# nano2.net
KiCad netlist of a schematic drawn in EAGLE
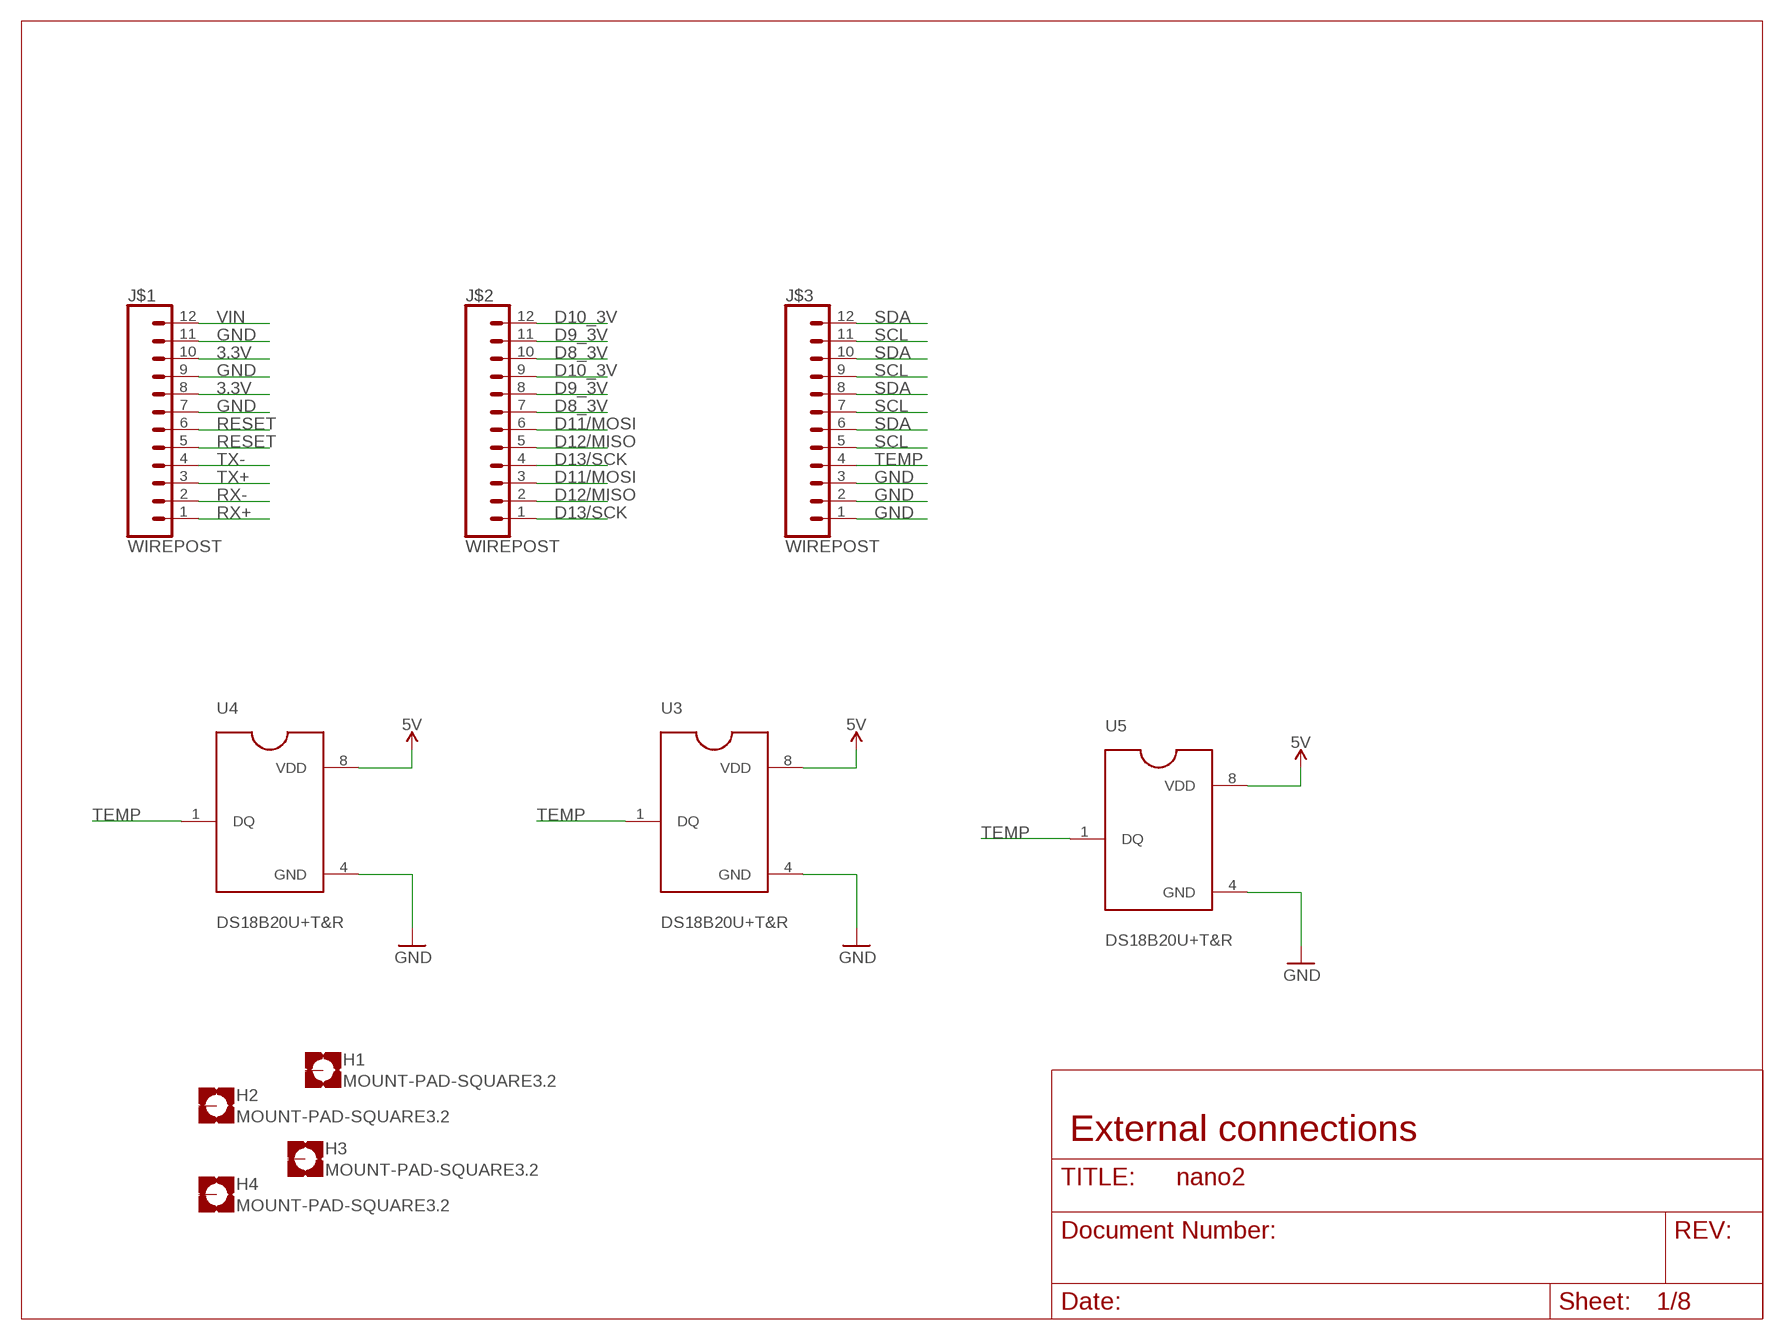
[diagram p0: schematic, sheet 1]
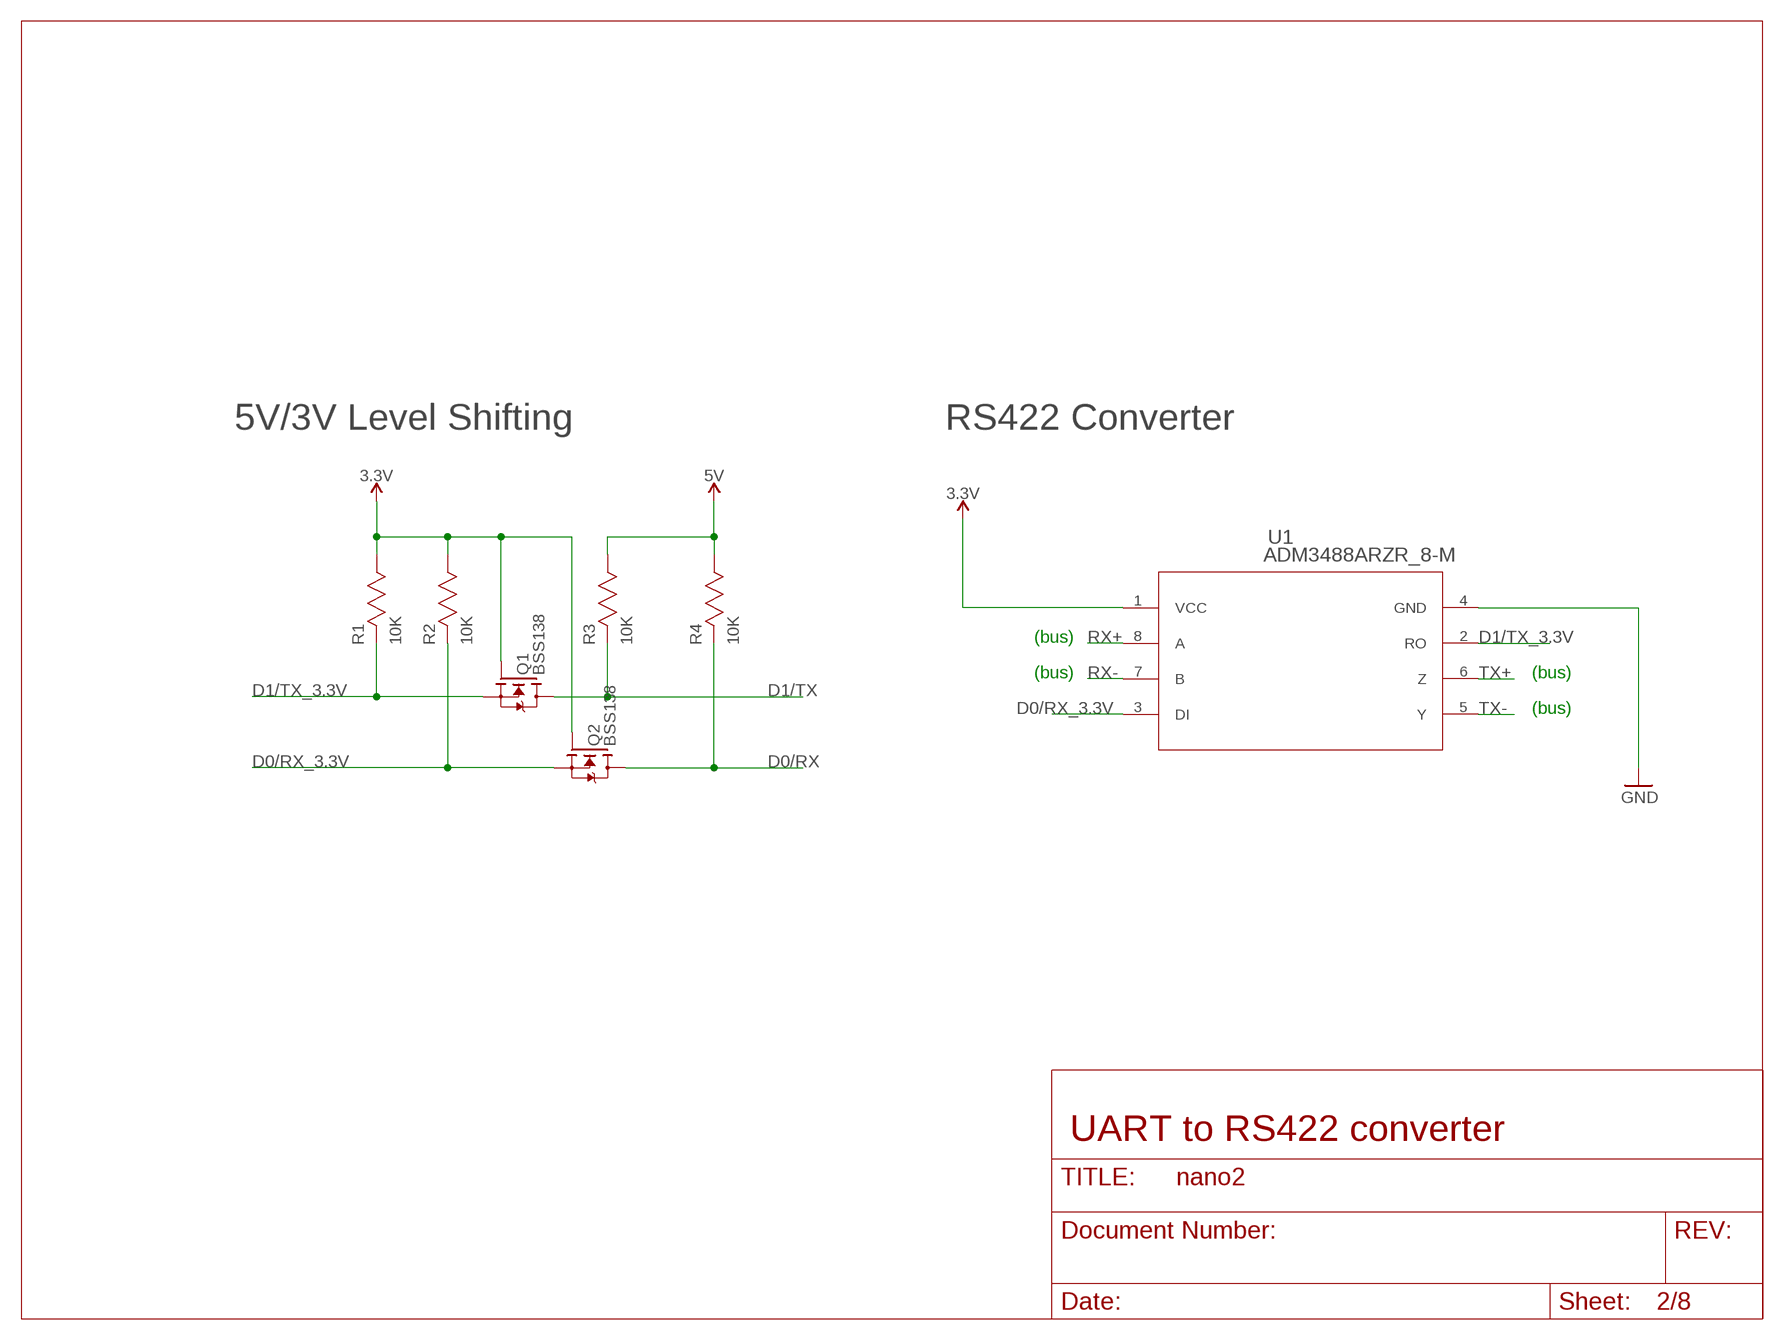
[diagram p1: schematic, sheet 2]
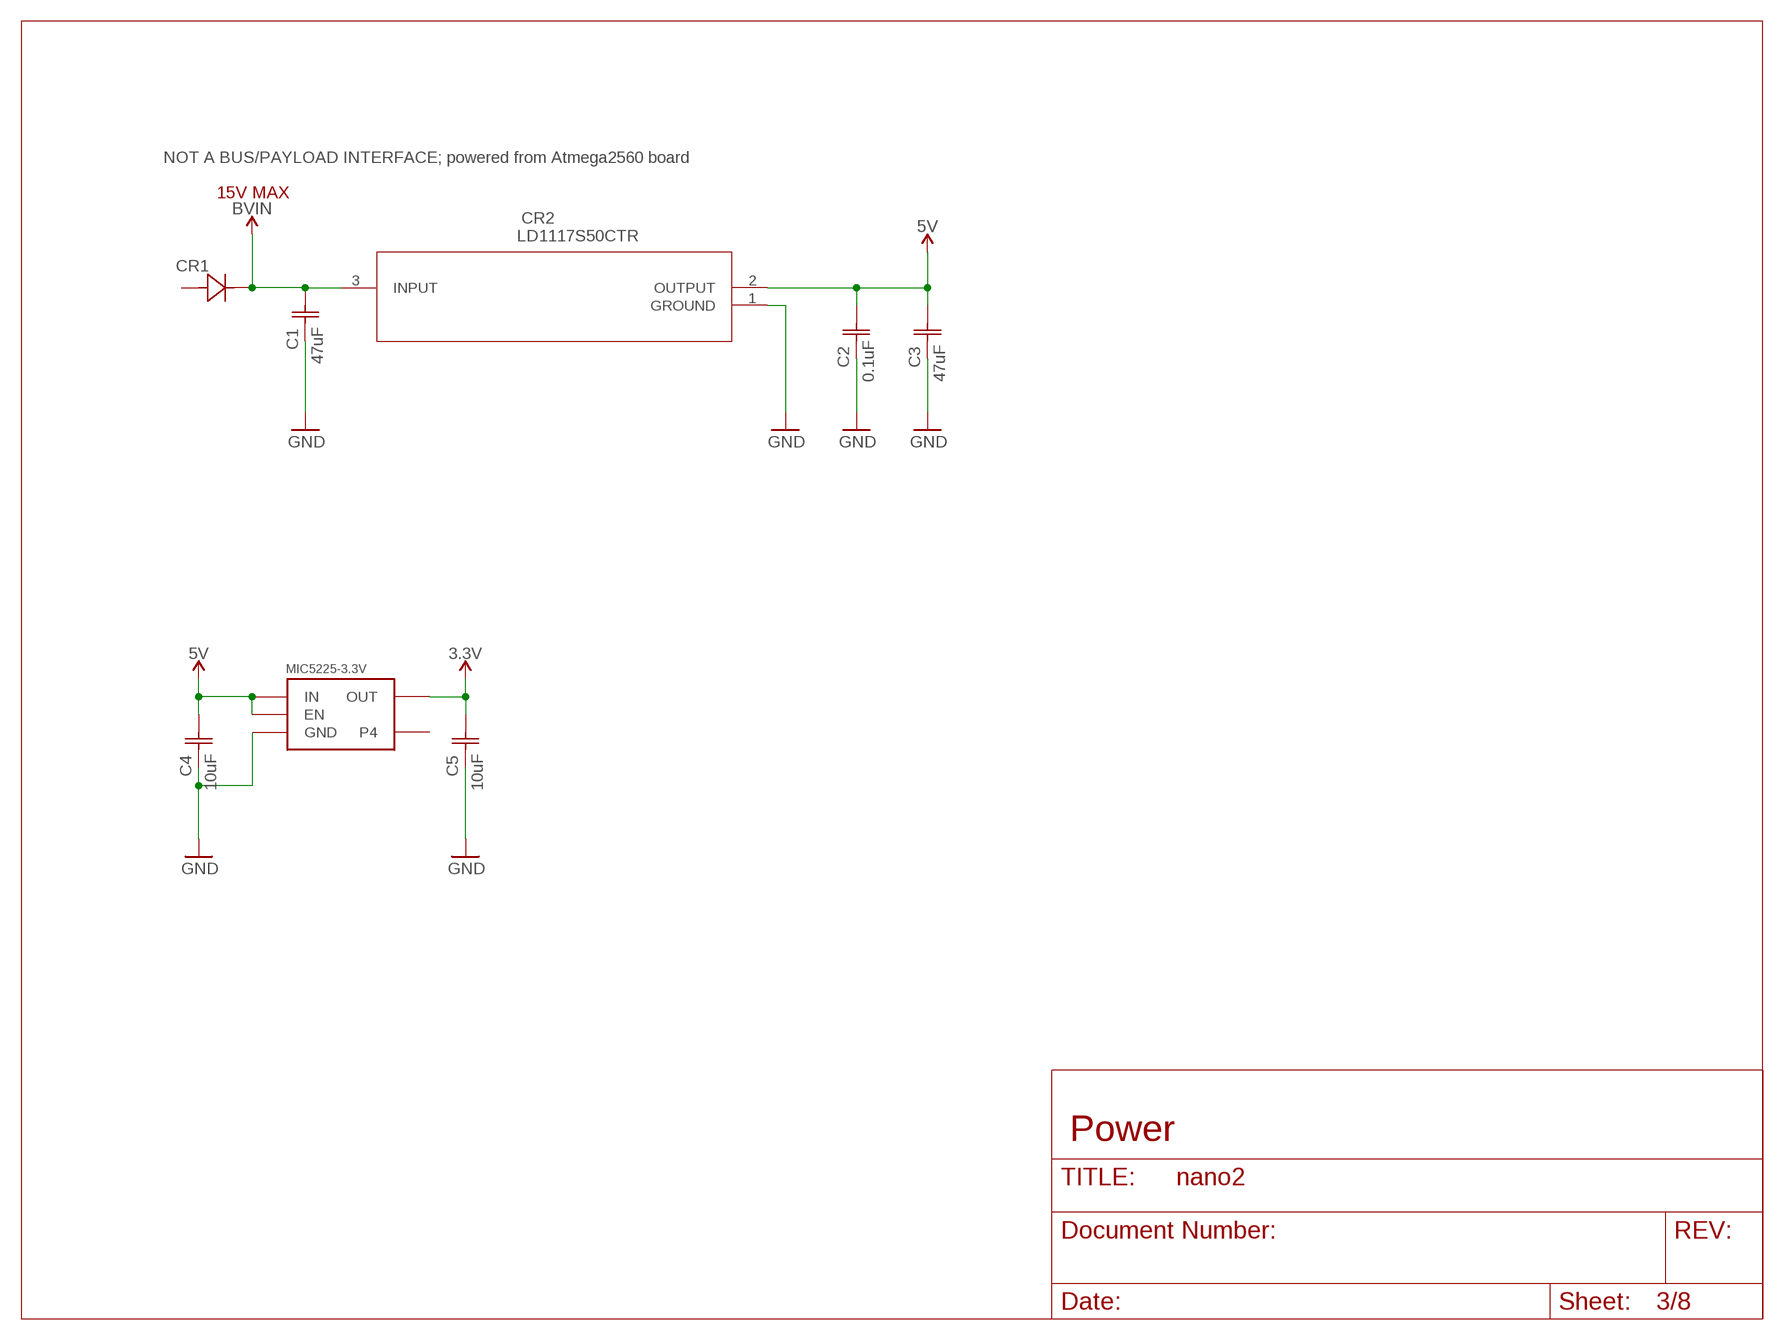
[diagram p2: schematic, sheet 3]
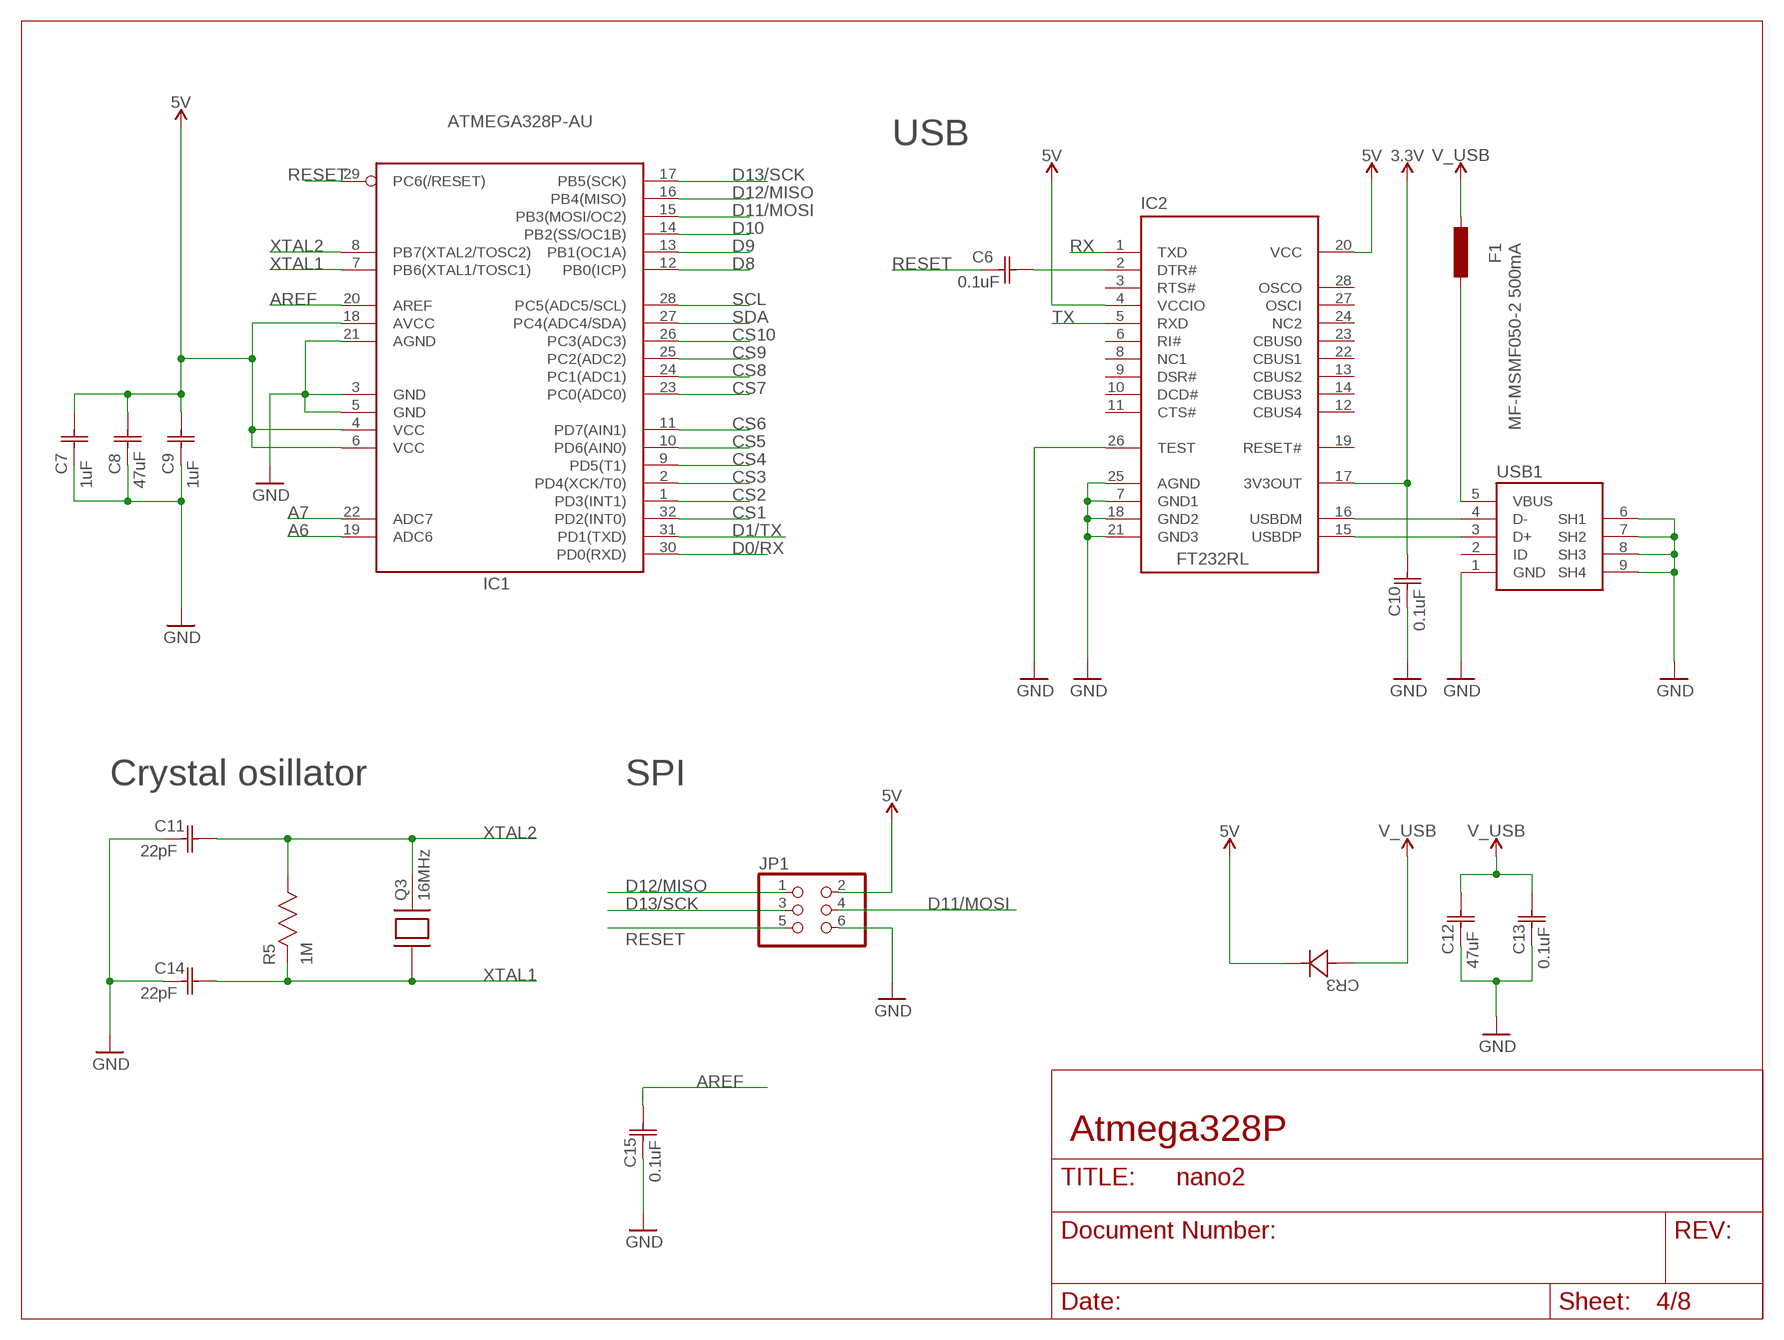
[diagram p3: schematic, sheet 4]
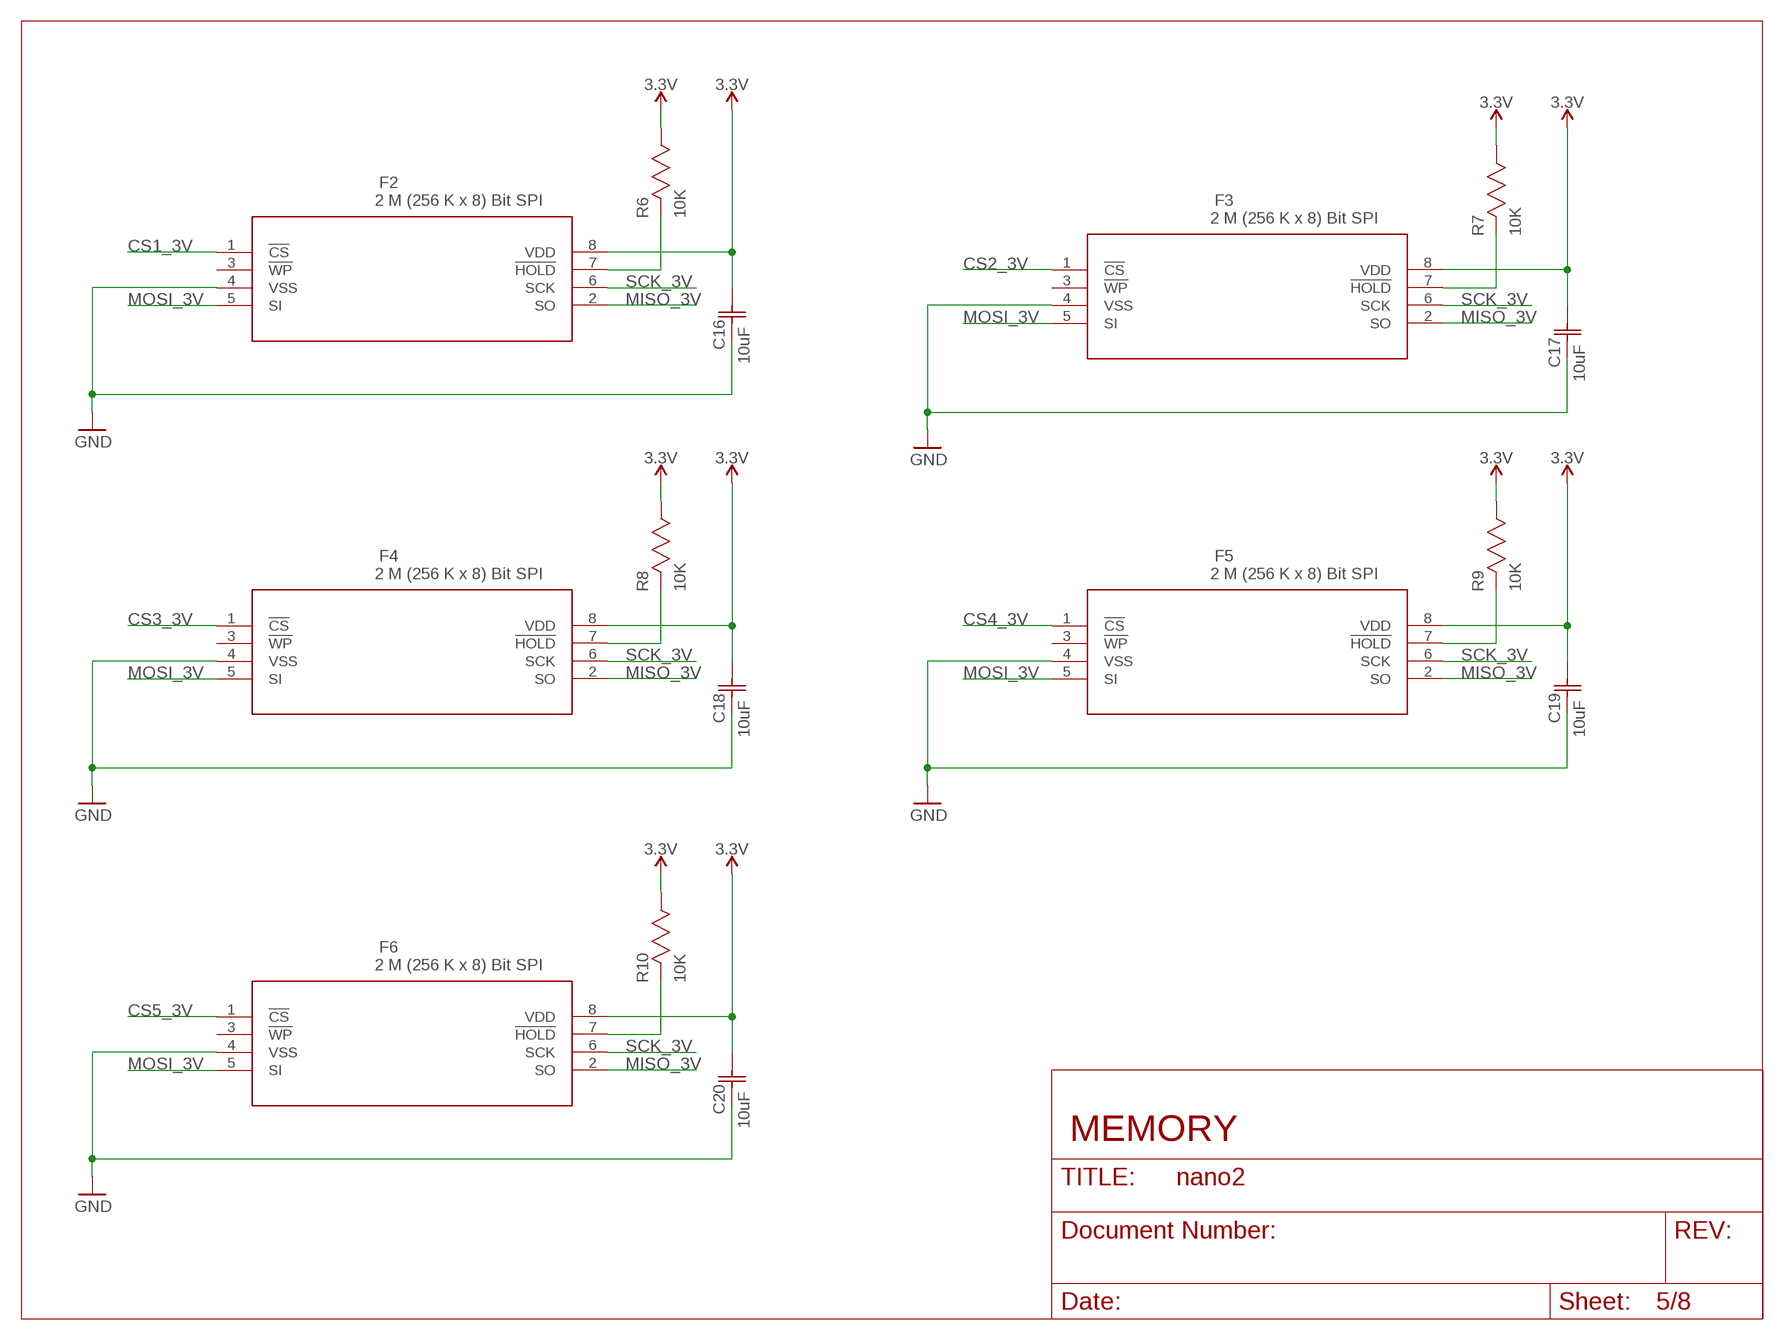
[diagram p4: schematic, sheet 5]
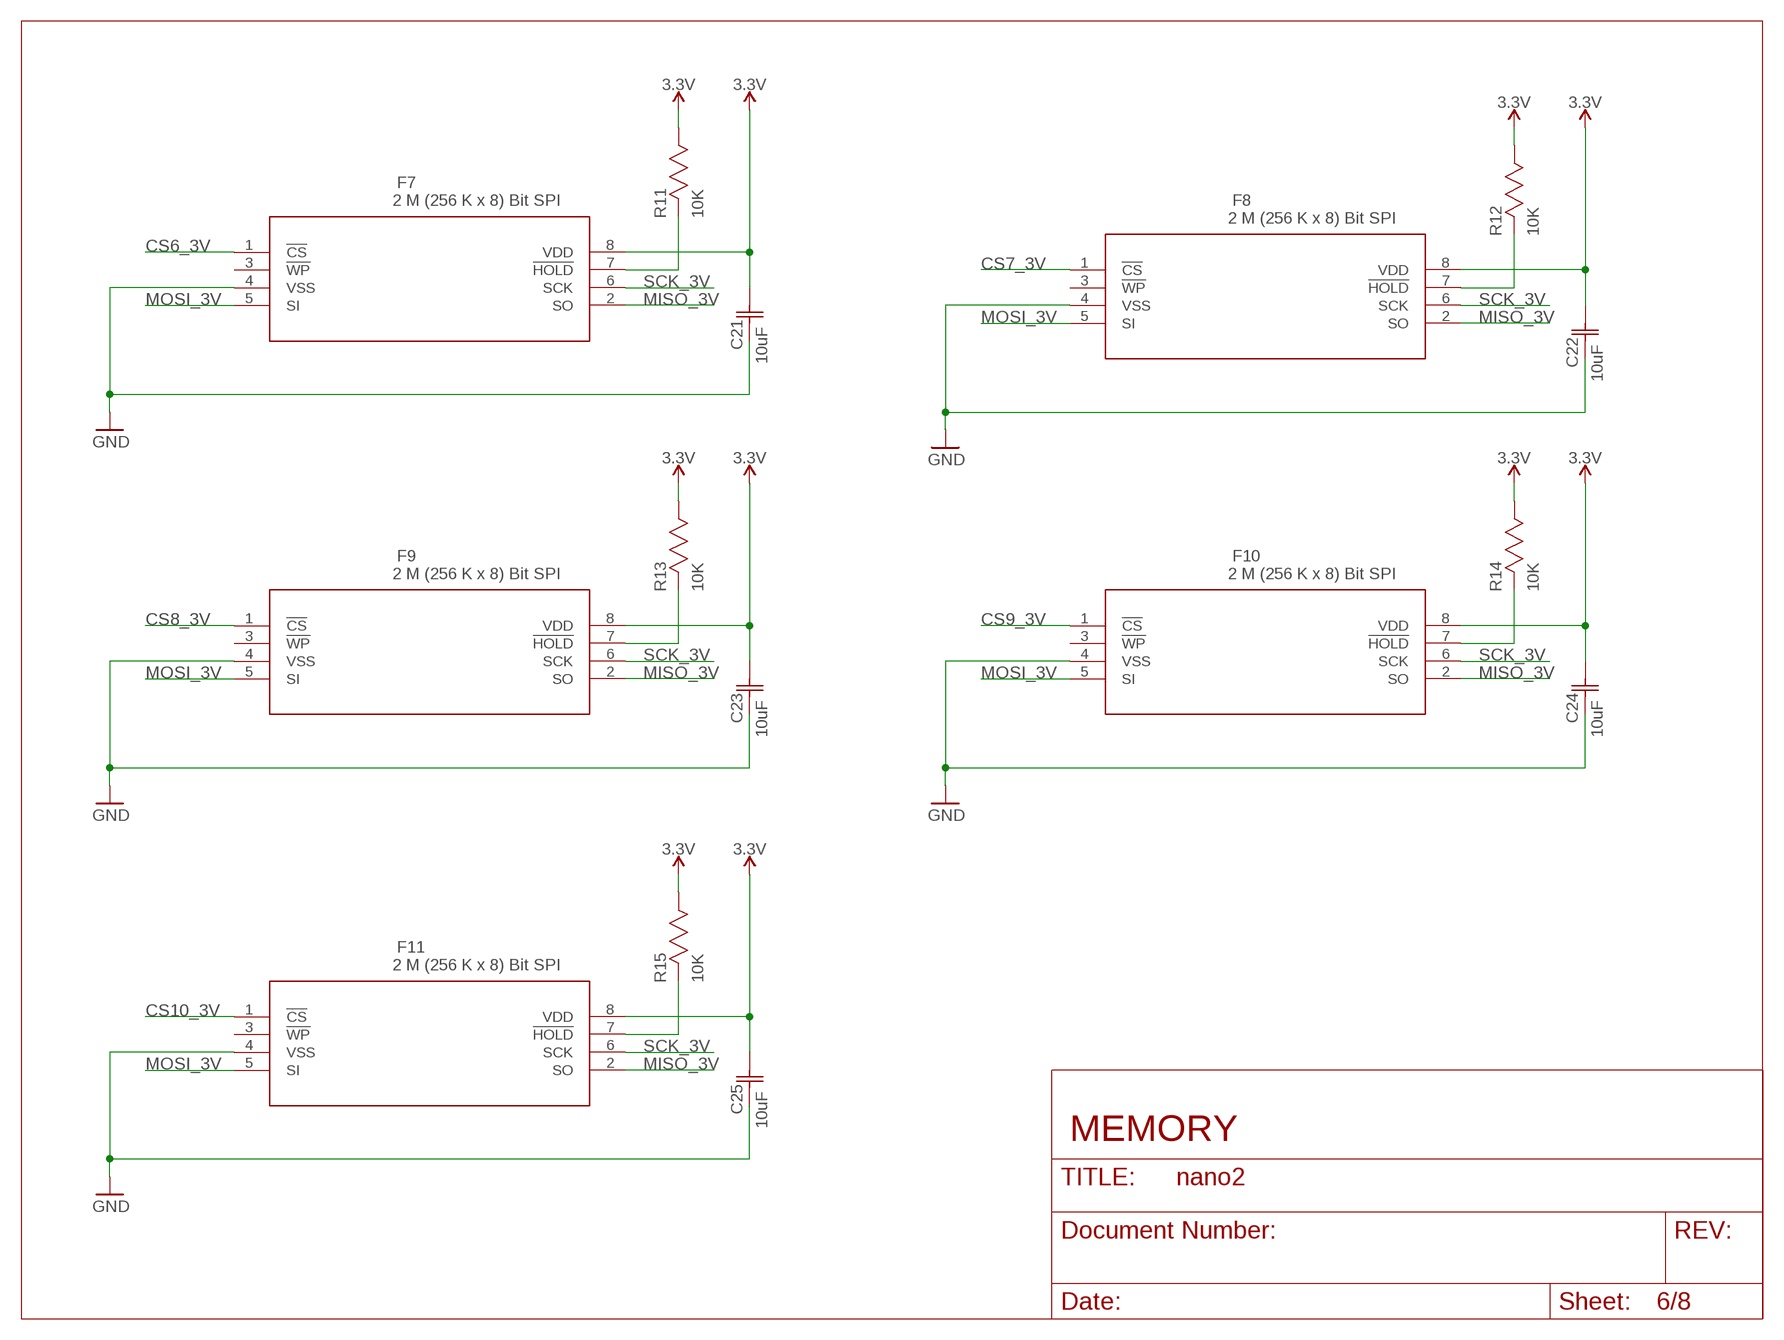
[diagram p5: schematic, sheet 6]
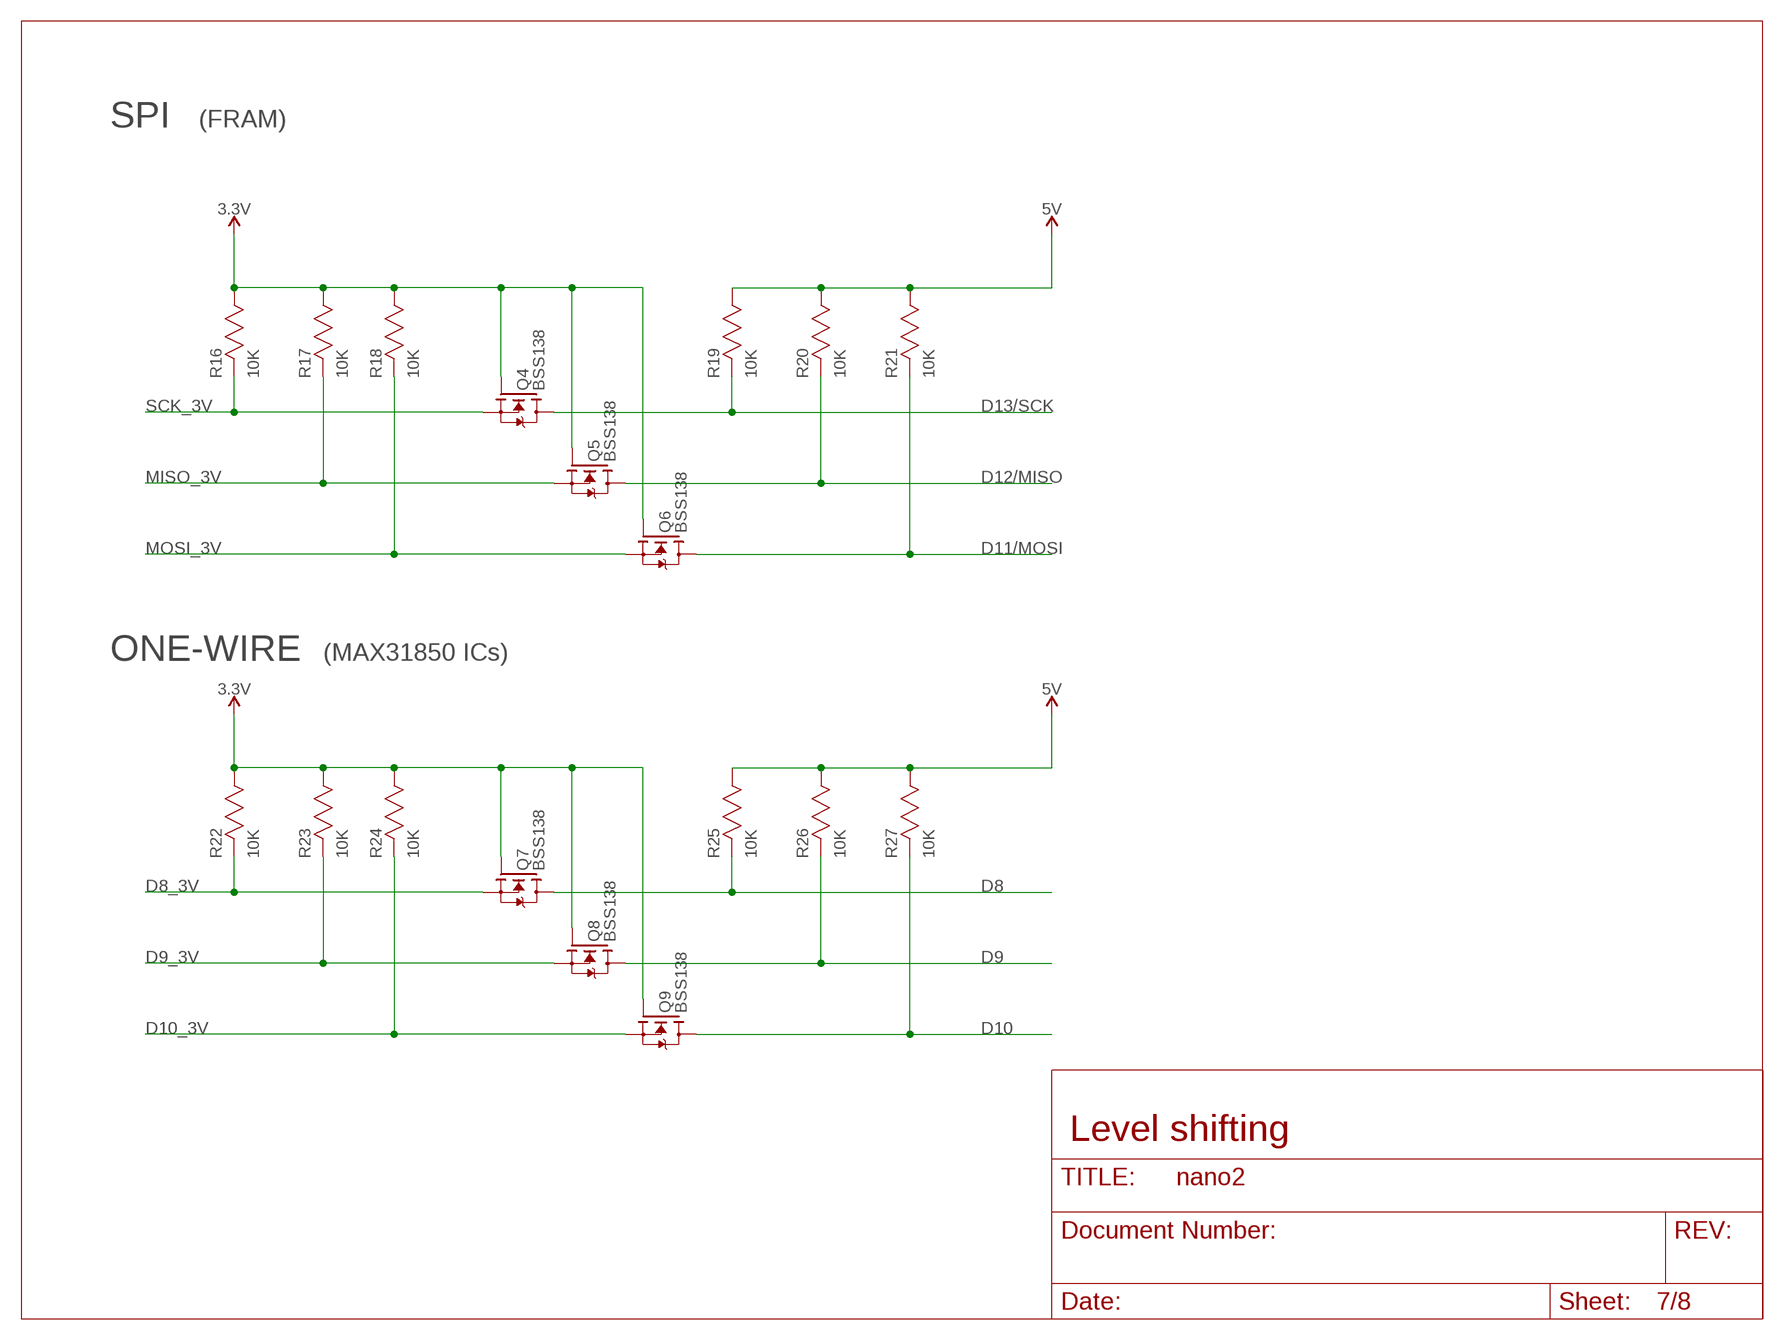
[diagram p6: schematic, sheet 7]
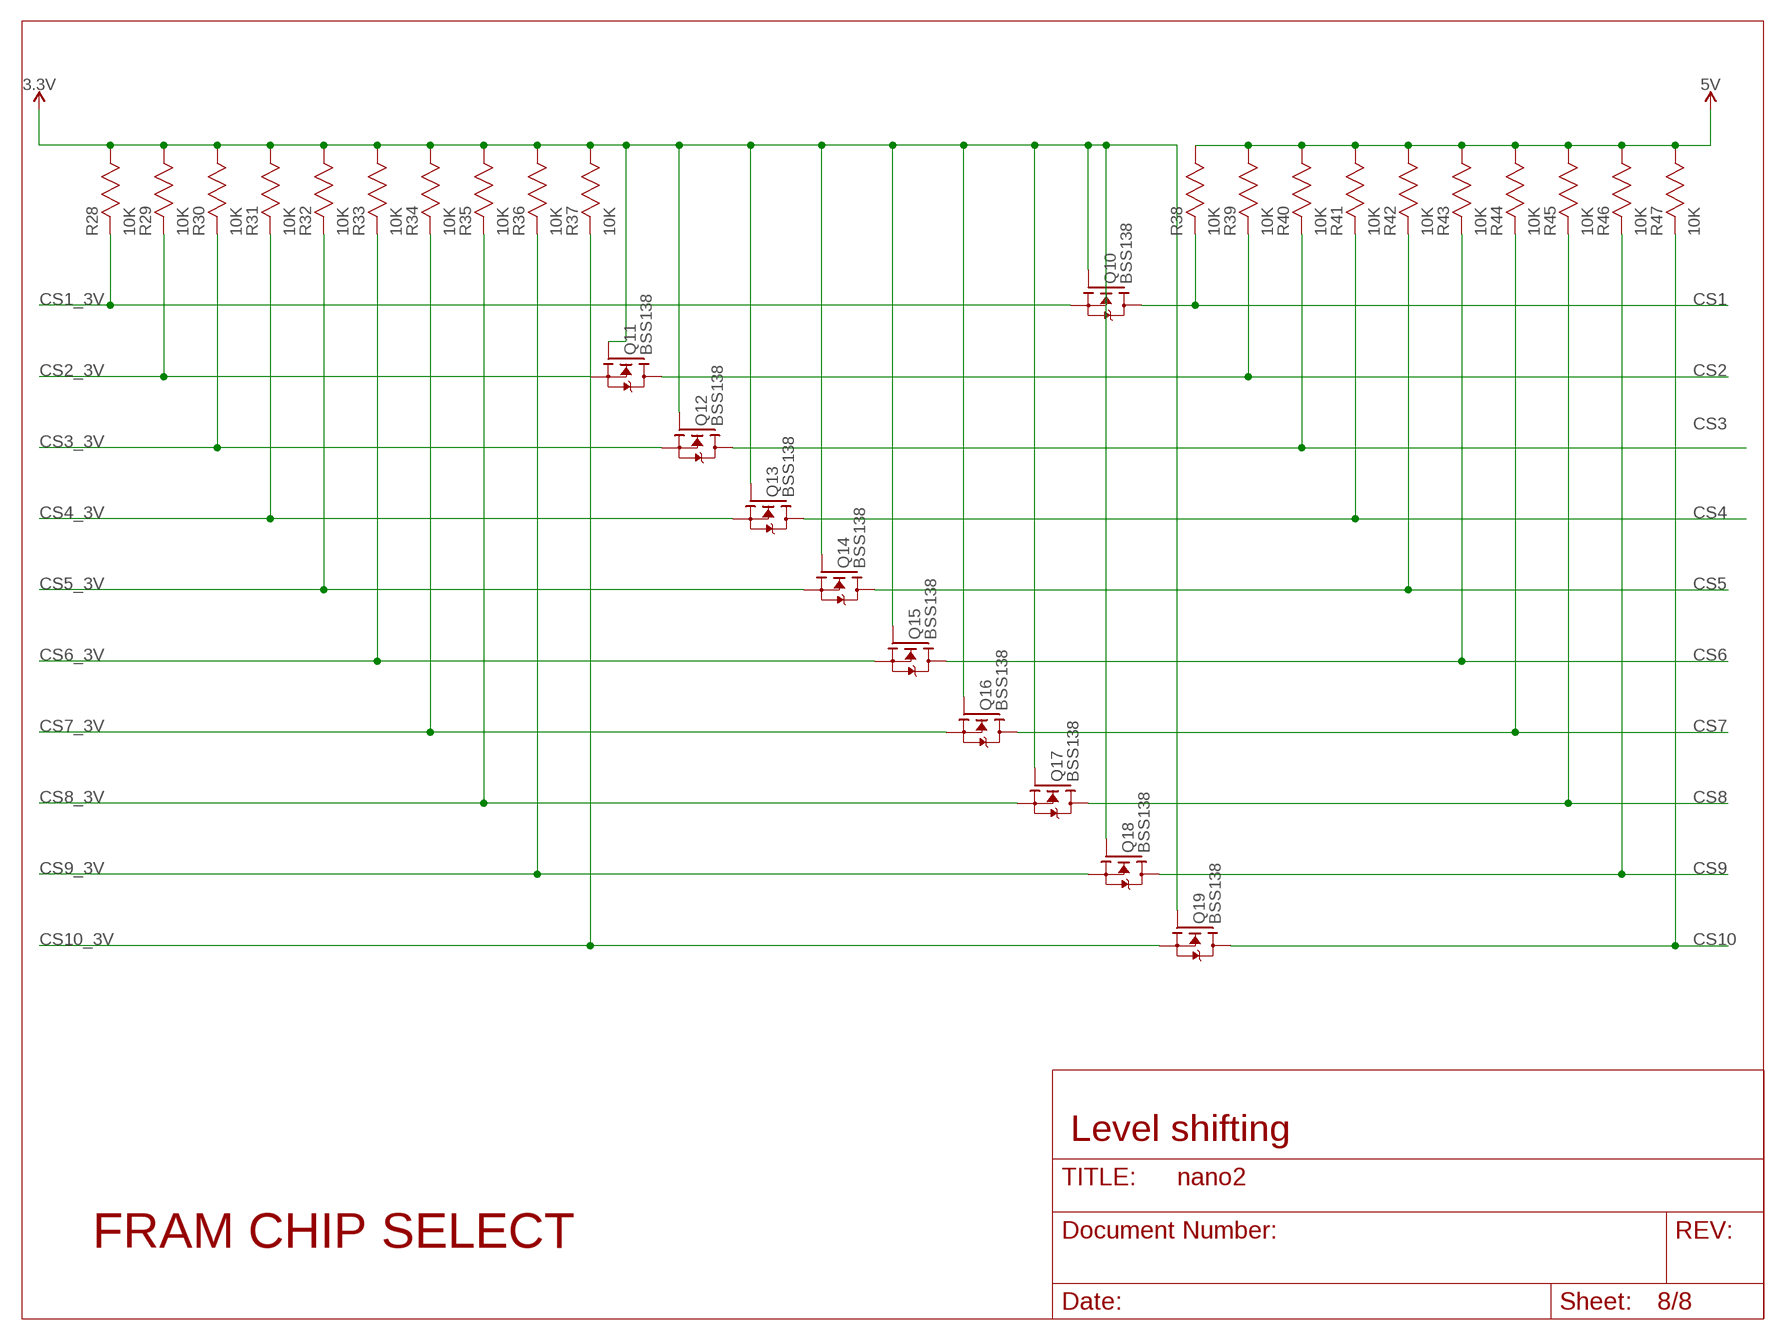
[diagram p7: schematic, sheet 8]

(export (version "E")
  (design (tool "Eeschema 10.0.6"))
  (components
    (comp (ref "C6")
      (value "0.1uF")
      (footprint "eagle-import:CAP_01")
      (fields (field (name "MANUFACTURER_PART_NUMBER") "CC0402KRX5R6BB104"))
      (libsource (lib "eagle-import") (part "CAP_01UF"))
    )
    (comp (ref "C7")
      (value "1uF")
      (footprint "eagle-import:YAG_CC0805")
      (fields (field (name "MANUFACTURER_PART_NUMBER") "CC0805KKX7R7BB105"))
      (libsource (lib "eagle-import") (part "CAP_1UF"))
    )
    (comp (ref "C8")
      (value "47uF")
      (footprint "eagle-import:CAP_5750")
      (fields (field (name "MANUFACTURER_PART_NUMBER") "CGA9N3X7R1C476M230KB"))
      (libsource (lib "eagle-import") (part "CAP_47UF"))
    )
    (comp (ref "C9")
      (value "1uF")
      (footprint "eagle-import:YAG_CC0805")
      (fields (field (name "MANUFACTURER_PART_NUMBER") "CC0805KKX7R7BB105"))
      (libsource (lib "eagle-import") (part "CAP_1UF"))
    )
    (comp (ref "C10")
      (value "0.1uF")
      (footprint "eagle-import:CAP_01")
      (fields (field (name "MANUFACTURER_PART_NUMBER") "CC0402KRX5R6BB104"))
      (libsource (lib "eagle-import") (part "CAP_01UF"))
    )
    (comp (ref "C11")
      (value "22pF")
      (footprint "eagle-import:CC0805N")
      (libsource (lib "eagle-import") (part "CAP_22PF"))
    )
    (comp (ref "C12")
      (value "47uF")
      (footprint "eagle-import:CAP_5750")
      (fields (field (name "MANUFACTURER_PART_NUMBER") "CGA9N3X7R1C476M230KB"))
      (libsource (lib "eagle-import") (part "CAP_47UF"))
    )
    (comp (ref "C13")
      (value "0.1uF")
      (footprint "eagle-import:CAP_01")
      (fields (field (name "MANUFACTURER_PART_NUMBER") "CC0402KRX5R6BB104"))
      (libsource (lib "eagle-import") (part "CAP_01UF"))
    )
    (comp (ref "C14")
      (value "22pF")
      (footprint "eagle-import:CC0805N")
      (libsource (lib "eagle-import") (part "CAP_22PF"))
    )
    (comp (ref "C15")
      (value "0.1uF")
      (footprint "eagle-import:CAP_01")
      (fields (field (name "MANUFACTURER_PART_NUMBER") "CC0402KRX5R6BB104"))
      (libsource (lib "eagle-import") (part "CAP_01UF"))
    )
    (comp (ref "CR3")
      (value "DIODE_600V_3A")
      (footprint "eagle-import:DIODE_600V_3A")
      (fields (field (name "MANUFACTURER_PART_NUMBER") "RS3JB13F"))
      (libsource (lib "eagle-import") (part "DIODE_600V_3A"))
    )
    (comp (ref "F1")
      (value "MF-MSMF050-2 500mA")
      (footprint "eagle-import:L1812")
      (fields (field (name "PART_NUMBER") "MF-MSMF050-2"))
      (libsource (lib "eagle-import") (part "0002_MF-MSMF050-2"))
    )
    (comp (ref "IC1")
      (value "ATMEGA328P-AU")
      (footprint "eagle-import:TQFP32-08")
      (libsource (lib "eagle-import") (part "0265_ATMEGA328P-AU"))
    )
    (comp (ref "IC2")
      (value "FT232RL")
      (footprint "eagle-import:SSOP28")
      (libsource (lib "eagle-import") (part "0226_FT232RL"))
    )
    (comp (ref "JP1")
      (value "0114_PH254-203DF118A00V")
      (footprint "eagle-import:2X03")
      (fields (field (name "PART_NUMBER") "PH254-203DF118A00V"))
      (libsource (lib "eagle-import") (part "0114_PH254-203DF118A00V"))
    )
    (comp (ref "Q3")
      (value "16MHz")
      (footprint "eagle-import:OSCILLATOR")
      (libsource (lib "eagle-import") (part "OSILLATOR"))
    )
    (comp (ref "R5")
      (value "1M")
      (footprint "eagle-import:RC0603N")
      (libsource (lib "eagle-import") (part "RES_1M"))
    )
    (comp (ref "USB1")
      (value "0219_14850")
      (footprint "eagle-import:USB-MINI-B_2")
      (fields (field (name "PART_NUMBER") "14850"))
      (libsource (lib "eagle-import") (part "0219_14850"))
    )
    (comp (ref "Q1")
      (value "BSS138")
      (footprint "eagle-import:SOT-23")
      (fields (field (name "MANUFACTURER_PART_NUMBER") "BSS138TA"))
      (libsource (lib "eagle-import") (part "BSS138"))
    )
    (comp (ref "Q2")
      (value "BSS138")
      (footprint "eagle-import:SOT-23")
      (fields (field (name "MANUFACTURER_PART_NUMBER") "BSS138TA"))
      (libsource (lib "eagle-import") (part "BSS138"))
    )
    (comp (ref "R1")
      (value "10K")
      (footprint "eagle-import:RC0603N")
      (libsource (lib "eagle-import") (part "RES_10K"))
    )
    (comp (ref "R2")
      (value "10K")
      (footprint "eagle-import:RC0603N")
      (libsource (lib "eagle-import") (part "RES_10K"))
    )
    (comp (ref "R3")
      (value "10K")
      (footprint "eagle-import:RC0603N")
      (libsource (lib "eagle-import") (part "RES_10K"))
    )
    (comp (ref "R4")
      (value "10K")
      (footprint "eagle-import:RC0603N")
      (libsource (lib "eagle-import") (part "RES_10K"))
    )
    (comp (ref "U1")
      (value "ADM3488ARZR_8-M")
      (footprint "eagle-import:R_8-M")
      (fields (field (name "MANUFACTURER_PART_NUMBER") "ADM3488ARZ"))
      (libsource (lib "eagle-import") (part "ADM3488ARZR_8-M"))
    )
    (comp (ref "C16")
      (value "10uF")
      (footprint "eagle-import:CAP_GRM219R61A106KE44D")
      (libsource (lib "eagle-import") (part "CAP_10UF"))
    )
    (comp (ref "C17")
      (value "10uF")
      (footprint "eagle-import:CAP_GRM219R61A106KE44D")
      (libsource (lib "eagle-import") (part "CAP_10UF"))
    )
    (comp (ref "C18")
      (value "10uF")
      (footprint "eagle-import:CAP_GRM219R61A106KE44D")
      (libsource (lib "eagle-import") (part "CAP_10UF"))
    )
    (comp (ref "C19")
      (value "10uF")
      (footprint "eagle-import:CAP_GRM219R61A106KE44D")
      (libsource (lib "eagle-import") (part "CAP_10UF"))
    )
    (comp (ref "C20")
      (value "10uF")
      (footprint "eagle-import:CAP_GRM219R61A106KE44D")
      (libsource (lib "eagle-import") (part "CAP_10UF"))
    )
    (comp (ref "F2")
      (value "2 M (256 K x 8) Bit SPI")
      (footprint "eagle-import:FRAM_MB85RS2MTA_FPT-8P-M09")
      (libsource (lib "eagle-import") (part "FRAM_MB85RS2MTA"))
    )
    (comp (ref "F3")
      (value "2 M (256 K x 8) Bit SPI")
      (footprint "eagle-import:FRAM_MB85RS2MTA_FPT-8P-M09")
      (libsource (lib "eagle-import") (part "FRAM_MB85RS2MTA"))
    )
    (comp (ref "F4")
      (value "2 M (256 K x 8) Bit SPI")
      (footprint "eagle-import:FRAM_MB85RS2MTA_FPT-8P-M09")
      (libsource (lib "eagle-import") (part "FRAM_MB85RS2MTA"))
    )
    (comp (ref "F5")
      (value "2 M (256 K x 8) Bit SPI")
      (footprint "eagle-import:FRAM_MB85RS2MTA_FPT-8P-M09")
      (libsource (lib "eagle-import") (part "FRAM_MB85RS2MTA"))
    )
    (comp (ref "F6")
      (value "2 M (256 K x 8) Bit SPI")
      (footprint "eagle-import:FRAM_MB85RS2MTA_FPT-8P-M09")
      (libsource (lib "eagle-import") (part "FRAM_MB85RS2MTA"))
    )
    (comp (ref "R6")
      (value "10K")
      (footprint "eagle-import:RC0603N")
      (libsource (lib "eagle-import") (part "RES_10K"))
    )
    (comp (ref "R7")
      (value "10K")
      (footprint "eagle-import:RC0603N")
      (libsource (lib "eagle-import") (part "RES_10K"))
    )
    (comp (ref "R8")
      (value "10K")
      (footprint "eagle-import:RC0603N")
      (libsource (lib "eagle-import") (part "RES_10K"))
    )
    (comp (ref "R9")
      (value "10K")
      (footprint "eagle-import:RC0603N")
      (libsource (lib "eagle-import") (part "RES_10K"))
    )
    (comp (ref "R10")
      (value "10K")
      (footprint "eagle-import:RC0603N")
      (libsource (lib "eagle-import") (part "RES_10K"))
    )
    (comp (ref "C21")
      (value "10uF")
      (footprint "eagle-import:CAP_GRM219R61A106KE44D")
      (libsource (lib "eagle-import") (part "CAP_10UF"))
    )
    (comp (ref "C22")
      (value "10uF")
      (footprint "eagle-import:CAP_GRM219R61A106KE44D")
      (libsource (lib "eagle-import") (part "CAP_10UF"))
    )
    (comp (ref "C23")
      (value "10uF")
      (footprint "eagle-import:CAP_GRM219R61A106KE44D")
      (libsource (lib "eagle-import") (part "CAP_10UF"))
    )
    (comp (ref "C24")
      (value "10uF")
      (footprint "eagle-import:CAP_GRM219R61A106KE44D")
      (libsource (lib "eagle-import") (part "CAP_10UF"))
    )
    (comp (ref "C25")
      (value "10uF")
      (footprint "eagle-import:CAP_GRM219R61A106KE44D")
      (libsource (lib "eagle-import") (part "CAP_10UF"))
    )
    (comp (ref "F7")
      (value "2 M (256 K x 8) Bit SPI")
      (footprint "eagle-import:FRAM_MB85RS2MTA_FPT-8P-M09")
      (libsource (lib "eagle-import") (part "FRAM_MB85RS2MTA"))
    )
    (comp (ref "F8")
      (value "2 M (256 K x 8) Bit SPI")
      (footprint "eagle-import:FRAM_MB85RS2MTA_FPT-8P-M09")
      (libsource (lib "eagle-import") (part "FRAM_MB85RS2MTA"))
    )
    (comp (ref "F9")
      (value "2 M (256 K x 8) Bit SPI")
      (footprint "eagle-import:FRAM_MB85RS2MTA_FPT-8P-M09")
      (libsource (lib "eagle-import") (part "FRAM_MB85RS2MTA"))
    )
    (comp (ref "F10")
      (value "2 M (256 K x 8) Bit SPI")
      (footprint "eagle-import:FRAM_MB85RS2MTA_FPT-8P-M09")
      (libsource (lib "eagle-import") (part "FRAM_MB85RS2MTA"))
    )
    (comp (ref "F11")
      (value "2 M (256 K x 8) Bit SPI")
      (footprint "eagle-import:FRAM_MB85RS2MTA_FPT-8P-M09")
      (libsource (lib "eagle-import") (part "FRAM_MB85RS2MTA"))
    )
    (comp (ref "R11")
      (value "10K")
      (footprint "eagle-import:RC0603N")
      (libsource (lib "eagle-import") (part "RES_10K"))
    )
    (comp (ref "R12")
      (value "10K")
      (footprint "eagle-import:RC0603N")
      (libsource (lib "eagle-import") (part "RES_10K"))
    )
    (comp (ref "R13")
      (value "10K")
      (footprint "eagle-import:RC0603N")
      (libsource (lib "eagle-import") (part "RES_10K"))
    )
    (comp (ref "R14")
      (value "10K")
      (footprint "eagle-import:RC0603N")
      (libsource (lib "eagle-import") (part "RES_10K"))
    )
    (comp (ref "R15")
      (value "10K")
      (footprint "eagle-import:RC0603N")
      (libsource (lib "eagle-import") (part "RES_10K"))
    )
    (comp (ref "H1")
      (value "MOUNT-PAD-SQUARE3.2")
      (footprint "eagle-import:3,2-PAD-SQUARE")
      (libsource (lib "eagle-import") (part "MOUNT-PAD-SQUARE3.2"))
    )
    (comp (ref "H2")
      (value "MOUNT-PAD-SQUARE3.2")
      (footprint "eagle-import:3,2-PAD-SQUARE")
      (libsource (lib "eagle-import") (part "MOUNT-PAD-SQUARE3.2"))
    )
    (comp (ref "H3")
      (value "MOUNT-PAD-SQUARE3.2")
      (footprint "eagle-import:3,2-PAD-SQUARE")
      (libsource (lib "eagle-import") (part "MOUNT-PAD-SQUARE3.2"))
    )
    (comp (ref "H4")
      (value "MOUNT-PAD-SQUARE3.2")
      (footprint "eagle-import:3,2-PAD-SQUARE")
      (libsource (lib "eagle-import") (part "MOUNT-PAD-SQUARE3.2"))
    )
    (comp (ref "J$1")
      (value "WIREPOST")
      (footprint "eagle-import:WIREWRAPPOST")
      (libsource (lib "eagle-import") (part "WIREPOST"))
    )
    (comp (ref "J$2")
      (value "WIREPOST")
      (footprint "eagle-import:WIREWRAPPOST")
      (libsource (lib "eagle-import") (part "WIREPOST"))
    )
    (comp (ref "J$3")
      (value "WIREPOST")
      (footprint "eagle-import:WIREWRAPPOST")
      (libsource (lib "eagle-import") (part "WIREPOST"))
    )
    (comp (ref "U3")
      (value "DS18B20U+T&R")
      (footprint "eagle-import:SOP65P500X110-8N")
      (fields (field (name "MF") "Maxim Integrated") (field (name "MP") "DS18B20U+T&amp;R"))
      (libsource (lib "eagle-import") (part "DS18B20U+T&R"))
    )
    (comp (ref "U4")
      (value "DS18B20U+T&R")
      (footprint "eagle-import:SOP65P500X110-8N")
      (fields (field (name "MF") "Maxim Integrated") (field (name "MP") "DS18B20U+T&amp;R"))
      (libsource (lib "eagle-import") (part "DS18B20U+T&R"))
    )
    (comp (ref "U5")
      (value "DS18B20U+T&R")
      (footprint "eagle-import:SOP65P500X110-8N")
      (fields (field (name "MF") "Maxim Integrated") (field (name "MP") "DS18B20U+T&amp;R"))
      (libsource (lib "eagle-import") (part "DS18B20U+T&R"))
    )
    (comp (ref "Q10")
      (value "BSS138")
      (footprint "eagle-import:SOT-23")
      (fields (field (name "MANUFACTURER_PART_NUMBER") "BSS138TA"))
      (libsource (lib "eagle-import") (part "BSS138"))
    )
    (comp (ref "Q11")
      (value "BSS138")
      (footprint "eagle-import:SOT-23")
      (fields (field (name "MANUFACTURER_PART_NUMBER") "BSS138TA"))
      (libsource (lib "eagle-import") (part "BSS138"))
    )
    (comp (ref "Q12")
      (value "BSS138")
      (footprint "eagle-import:SOT-23")
      (fields (field (name "MANUFACTURER_PART_NUMBER") "BSS138TA"))
      (libsource (lib "eagle-import") (part "BSS138"))
    )
    (comp (ref "Q13")
      (value "BSS138")
      (footprint "eagle-import:SOT-23")
      (fields (field (name "MANUFACTURER_PART_NUMBER") "BSS138TA"))
      (libsource (lib "eagle-import") (part "BSS138"))
    )
    (comp (ref "Q14")
      (value "BSS138")
      (footprint "eagle-import:SOT-23")
      (fields (field (name "MANUFACTURER_PART_NUMBER") "BSS138TA"))
      (libsource (lib "eagle-import") (part "BSS138"))
    )
    (comp (ref "Q15")
      (value "BSS138")
      (footprint "eagle-import:SOT-23")
      (fields (field (name "MANUFACTURER_PART_NUMBER") "BSS138TA"))
      (libsource (lib "eagle-import") (part "BSS138"))
    )
    (comp (ref "Q16")
      (value "BSS138")
      (footprint "eagle-import:SOT-23")
      (fields (field (name "MANUFACTURER_PART_NUMBER") "BSS138TA"))
      (libsource (lib "eagle-import") (part "BSS138"))
    )
    (comp (ref "Q17")
      (value "BSS138")
      (footprint "eagle-import:SOT-23")
      (fields (field (name "MANUFACTURER_PART_NUMBER") "BSS138TA"))
      (libsource (lib "eagle-import") (part "BSS138"))
    )
    (comp (ref "Q18")
      (value "BSS138")
      (footprint "eagle-import:SOT-23")
      (fields (field (name "MANUFACTURER_PART_NUMBER") "BSS138TA"))
      (libsource (lib "eagle-import") (part "BSS138"))
    )
    (comp (ref "Q19")
      (value "BSS138")
      (footprint "eagle-import:SOT-23")
      (fields (field (name "MANUFACTURER_PART_NUMBER") "BSS138TA"))
      (libsource (lib "eagle-import") (part "BSS138"))
    )
    (comp (ref "R28")
      (value "10K")
      (footprint "eagle-import:RC0603N")
      (libsource (lib "eagle-import") (part "RES_10K"))
    )
    (comp (ref "R29")
      (value "10K")
      (footprint "eagle-import:RC0603N")
      (libsource (lib "eagle-import") (part "RES_10K"))
    )
    (comp (ref "R30")
      (value "10K")
      (footprint "eagle-import:RC0603N")
      (libsource (lib "eagle-import") (part "RES_10K"))
    )
    (comp (ref "R31")
      (value "10K")
      (footprint "eagle-import:RC0603N")
      (libsource (lib "eagle-import") (part "RES_10K"))
    )
    (comp (ref "R32")
      (value "10K")
      (footprint "eagle-import:RC0603N")
      (libsource (lib "eagle-import") (part "RES_10K"))
    )
    (comp (ref "R33")
      (value "10K")
      (footprint "eagle-import:RC0603N")
      (libsource (lib "eagle-import") (part "RES_10K"))
    )
    (comp (ref "R34")
      (value "10K")
      (footprint "eagle-import:RC0603N")
      (libsource (lib "eagle-import") (part "RES_10K"))
    )
    (comp (ref "R35")
      (value "10K")
      (footprint "eagle-import:RC0603N")
      (libsource (lib "eagle-import") (part "RES_10K"))
    )
    (comp (ref "R36")
      (value "10K")
      (footprint "eagle-import:RC0603N")
      (libsource (lib "eagle-import") (part "RES_10K"))
    )
    (comp (ref "R37")
      (value "10K")
      (footprint "eagle-import:RC0603N")
      (libsource (lib "eagle-import") (part "RES_10K"))
    )
    (comp (ref "R38")
      (value "10K")
      (footprint "eagle-import:RC0603N")
      (libsource (lib "eagle-import") (part "RES_10K"))
    )
    (comp (ref "R39")
      (value "10K")
      (footprint "eagle-import:RC0603N")
      (libsource (lib "eagle-import") (part "RES_10K"))
    )
    (comp (ref "R40")
      (value "10K")
      (footprint "eagle-import:RC0603N")
      (libsource (lib "eagle-import") (part "RES_10K"))
    )
    (comp (ref "R41")
      (value "10K")
      (footprint "eagle-import:RC0603N")
      (libsource (lib "eagle-import") (part "RES_10K"))
    )
    (comp (ref "R42")
      (value "10K")
      (footprint "eagle-import:RC0603N")
      (libsource (lib "eagle-import") (part "RES_10K"))
    )
    (comp (ref "R43")
      (value "10K")
      (footprint "eagle-import:RC0603N")
      (libsource (lib "eagle-import") (part "RES_10K"))
    )
    (comp (ref "R44")
      (value "10K")
      (footprint "eagle-import:RC0603N")
      (libsource (lib "eagle-import") (part "RES_10K"))
    )
    (comp (ref "R45")
      (value "10K")
      (footprint "eagle-import:RC0603N")
      (libsource (lib "eagle-import") (part "RES_10K"))
    )
    (comp (ref "R46")
      (value "10K")
      (footprint "eagle-import:RC0603N")
      (libsource (lib "eagle-import") (part "RES_10K"))
    )
    (comp (ref "R47")
      (value "10K")
      (footprint "eagle-import:RC0603N")
      (libsource (lib "eagle-import") (part "RES_10K"))
    )
    (comp (ref "C1")
      (value "47uF")
      (footprint "eagle-import:CAP_5750")
      (fields (field (name "MANUFACTURER_PART_NUMBER") "CGA9N3X7R1C476M230KB"))
      (libsource (lib "eagle-import") (part "CAP_47UF"))
    )
    (comp (ref "C2")
      (value "0.1uF")
      (footprint "eagle-import:CAP_01")
      (fields (field (name "MANUFACTURER_PART_NUMBER") "CC0402KRX5R6BB104"))
      (libsource (lib "eagle-import") (part "CAP_01UF"))
    )
    (comp (ref "C3")
      (value "47uF")
      (footprint "eagle-import:CAP_5750")
      (fields (field (name "MANUFACTURER_PART_NUMBER") "CGA9N3X7R1C476M230KB"))
      (libsource (lib "eagle-import") (part "CAP_47UF"))
    )
    (comp (ref "C4")
      (value "10uF")
      (footprint "eagle-import:CAP_GRM219R61A106KE44D")
      (libsource (lib "eagle-import") (part "CAP_10UF"))
    )
    (comp (ref "C5")
      (value "10uF")
      (footprint "eagle-import:CAP_GRM219R61A106KE44D")
      (libsource (lib "eagle-import") (part "CAP_10UF"))
    )
    (comp (ref "CR1")
      (value "DIODE_600V_3A")
      (footprint "eagle-import:DIODE_600V_3A")
      (fields (field (name "MANUFACTURER_PART_NUMBER") "RS3JB13F"))
      (libsource (lib "eagle-import") (part "DIODE_600V_3A"))
    )
    (comp (ref "CR2")
      (value "LD1117S50CTR")
      (footprint "eagle-import:SOT-223")
      (libsource (lib "eagle-import") (part "LD1117S50CTR"))
    )
    (comp (ref "U2")
      (value "MIC5225-3.3V")
      (footprint "eagle-import:SOT23-5")
      (libsource (lib "eagle-import") (part "MIC5225"))
    )
    (comp (ref "Q4")
      (value "BSS138")
      (footprint "eagle-import:SOT-23")
      (fields (field (name "MANUFACTURER_PART_NUMBER") "BSS138TA"))
      (libsource (lib "eagle-import") (part "BSS138"))
    )
    (comp (ref "Q5")
      (value "BSS138")
      (footprint "eagle-import:SOT-23")
      (fields (field (name "MANUFACTURER_PART_NUMBER") "BSS138TA"))
      (libsource (lib "eagle-import") (part "BSS138"))
    )
    (comp (ref "Q6")
      (value "BSS138")
      (footprint "eagle-import:SOT-23")
      (fields (field (name "MANUFACTURER_PART_NUMBER") "BSS138TA"))
      (libsource (lib "eagle-import") (part "BSS138"))
    )
    (comp (ref "Q7")
      (value "BSS138")
      (footprint "eagle-import:SOT-23")
      (fields (field (name "MANUFACTURER_PART_NUMBER") "BSS138TA"))
      (libsource (lib "eagle-import") (part "BSS138"))
    )
    (comp (ref "Q8")
      (value "BSS138")
      (footprint "eagle-import:SOT-23")
      (fields (field (name "MANUFACTURER_PART_NUMBER") "BSS138TA"))
      (libsource (lib "eagle-import") (part "BSS138"))
    )
    (comp (ref "Q9")
      (value "BSS138")
      (footprint "eagle-import:SOT-23")
      (fields (field (name "MANUFACTURER_PART_NUMBER") "BSS138TA"))
      (libsource (lib "eagle-import") (part "BSS138"))
    )
    (comp (ref "R16")
      (value "10K")
      (footprint "eagle-import:RC0603N")
      (libsource (lib "eagle-import") (part "RES_10K"))
    )
    (comp (ref "R17")
      (value "10K")
      (footprint "eagle-import:RC0603N")
      (libsource (lib "eagle-import") (part "RES_10K"))
    )
    (comp (ref "R18")
      (value "10K")
      (footprint "eagle-import:RC0603N")
      (libsource (lib "eagle-import") (part "RES_10K"))
    )
    (comp (ref "R19")
      (value "10K")
      (footprint "eagle-import:RC0603N")
      (libsource (lib "eagle-import") (part "RES_10K"))
    )
    (comp (ref "R20")
      (value "10K")
      (footprint "eagle-import:RC0603N")
      (libsource (lib "eagle-import") (part "RES_10K"))
    )
    (comp (ref "R21")
      (value "10K")
      (footprint "eagle-import:RC0603N")
      (libsource (lib "eagle-import") (part "RES_10K"))
    )
    (comp (ref "R22")
      (value "10K")
      (footprint "eagle-import:RC0603N")
      (libsource (lib "eagle-import") (part "RES_10K"))
    )
    (comp (ref "R23")
      (value "10K")
      (footprint "eagle-import:RC0603N")
      (libsource (lib "eagle-import") (part "RES_10K"))
    )
    (comp (ref "R24")
      (value "10K")
      (footprint "eagle-import:RC0603N")
      (libsource (lib "eagle-import") (part "RES_10K"))
    )
    (comp (ref "R25")
      (value "10K")
      (footprint "eagle-import:RC0603N")
      (libsource (lib "eagle-import") (part "RES_10K"))
    )
    (comp (ref "R26")
      (value "10K")
      (footprint "eagle-import:RC0603N")
      (libsource (lib "eagle-import") (part "RES_10K"))
    )
    (comp (ref "R27")
      (value "10K")
      (footprint "eagle-import:RC0603N")
      (libsource (lib "eagle-import") (part "RES_10K"))
    )
  )
  (nets
    (net (code "1") (name "3.3V") (class "Default")
      (node (ref "C10") (pin "2") (pinfunction "2_2") (pintype "passive"))
      (node (ref "C16") (pin "2") (pinfunction "2_2") (pintype "passive"))
      (node (ref "C17") (pin "2") (pinfunction "2_2") (pintype "passive"))
      (node (ref "C18") (pin "2") (pinfunction "2_2") (pintype "passive"))
      (node (ref "C19") (pin "2") (pinfunction "2_2") (pintype "passive"))
      (node (ref "C20") (pin "2") (pinfunction "2_2") (pintype "passive"))
      (node (ref "C21") (pin "2") (pinfunction "2_2") (pintype "passive"))
      (node (ref "C22") (pin "2") (pinfunction "2_2") (pintype "passive"))
      (node (ref "C23") (pin "2") (pinfunction "2_2") (pintype "passive"))
      (node (ref "C24") (pin "2") (pinfunction "2_2") (pintype "passive"))
      (node (ref "C25") (pin "2") (pinfunction "2_2") (pintype "passive"))
      (node (ref "C5") (pin "2") (pinfunction "2_2") (pintype "passive"))
      (node (ref "F10") (pin "8") (pinfunction "VDD_8") (pintype "passive"))
      (node (ref "F11") (pin "8") (pinfunction "VDD_8") (pintype "passive"))
      (node (ref "F2") (pin "8") (pinfunction "VDD_8") (pintype "passive"))
      (node (ref "F3") (pin "8") (pinfunction "VDD_8") (pintype "passive"))
      (node (ref "F4") (pin "8") (pinfunction "VDD_8") (pintype "passive"))
      (node (ref "F5") (pin "8") (pinfunction "VDD_8") (pintype "passive"))
      (node (ref "F6") (pin "8") (pinfunction "VDD_8") (pintype "passive"))
      (node (ref "F7") (pin "8") (pinfunction "VDD_8") (pintype "passive"))
      (node (ref "F8") (pin "8") (pinfunction "VDD_8") (pintype "passive"))
      (node (ref "F9") (pin "8") (pinfunction "VDD_8") (pintype "passive"))
      (node (ref "IC2") (pin "17") (pinfunction "3V3OUT_17") (pintype "power_in"))
      (node (ref "J$1") (pin "10") (pinfunction "10_10") (pintype "passive"))
      (node (ref "J$1") (pin "8") (pinfunction "8_8") (pintype "passive"))
      (node (ref "Q1") (pin "G") (pinfunction "G_G") (pintype "passive"))
      (node (ref "Q10") (pin "G") (pinfunction "G_G") (pintype "passive"))
      (node (ref "Q11") (pin "G") (pinfunction "G_G") (pintype "passive"))
      (node (ref "Q12") (pin "G") (pinfunction "G_G") (pintype "passive"))
      (node (ref "Q13") (pin "G") (pinfunction "G_G") (pintype "passive"))
      (node (ref "Q14") (pin "G") (pinfunction "G_G") (pintype "passive"))
      (node (ref "Q15") (pin "G") (pinfunction "G_G") (pintype "passive"))
      (node (ref "Q16") (pin "G") (pinfunction "G_G") (pintype "passive"))
      (node (ref "Q17") (pin "G") (pinfunction "G_G") (pintype "passive"))
      (node (ref "Q18") (pin "G") (pinfunction "G_G") (pintype "passive"))
      (node (ref "Q19") (pin "G") (pinfunction "G_G") (pintype "passive"))
      (node (ref "Q2") (pin "G") (pinfunction "G_G") (pintype "passive"))
      (node (ref "Q4") (pin "G") (pinfunction "G_G") (pintype "passive"))
      (node (ref "Q5") (pin "G") (pinfunction "G_G") (pintype "passive"))
      (node (ref "Q6") (pin "G") (pinfunction "G_G") (pintype "passive"))
      (node (ref "Q7") (pin "G") (pinfunction "G_G") (pintype "passive"))
      (node (ref "Q8") (pin "G") (pinfunction "G_G") (pintype "passive"))
      (node (ref "Q9") (pin "G") (pinfunction "G_G") (pintype "passive"))
      (node (ref "R1") (pin "1") (pinfunction "11_1") (pintype "passive"))
      (node (ref "R10") (pin "1") (pinfunction "11_1") (pintype "passive"))
      (node (ref "R11") (pin "1") (pinfunction "11_1") (pintype "passive"))
      (node (ref "R12") (pin "1") (pinfunction "11_1") (pintype "passive"))
      (node (ref "R13") (pin "1") (pinfunction "11_1") (pintype "passive"))
      (node (ref "R14") (pin "1") (pinfunction "11_1") (pintype "passive"))
      (node (ref "R15") (pin "1") (pinfunction "11_1") (pintype "passive"))
      (node (ref "R16") (pin "1") (pinfunction "11_1") (pintype "passive"))
      (node (ref "R17") (pin "1") (pinfunction "11_1") (pintype "passive"))
      (node (ref "R18") (pin "1") (pinfunction "11_1") (pintype "passive"))
      (node (ref "R2") (pin "1") (pinfunction "11_1") (pintype "passive"))
      (node (ref "R22") (pin "1") (pinfunction "11_1") (pintype "passive"))
      (node (ref "R23") (pin "1") (pinfunction "11_1") (pintype "passive"))
      (node (ref "R24") (pin "1") (pinfunction "11_1") (pintype "passive"))
      (node (ref "R28") (pin "1") (pinfunction "11_1") (pintype "passive"))
      (node (ref "R29") (pin "1") (pinfunction "11_1") (pintype "passive"))
      (node (ref "R30") (pin "1") (pinfunction "11_1") (pintype "passive"))
      (node (ref "R31") (pin "1") (pinfunction "11_1") (pintype "passive"))
      (node (ref "R32") (pin "1") (pinfunction "11_1") (pintype "passive"))
      (node (ref "R33") (pin "1") (pinfunction "11_1") (pintype "passive"))
      (node (ref "R34") (pin "1") (pinfunction "11_1") (pintype "passive"))
      (node (ref "R35") (pin "1") (pinfunction "11_1") (pintype "passive"))
      (node (ref "R36") (pin "1") (pinfunction "11_1") (pintype "passive"))
      (node (ref "R37") (pin "1") (pinfunction "11_1") (pintype "passive"))
      (node (ref "R6") (pin "1") (pinfunction "11_1") (pintype "passive"))
      (node (ref "R7") (pin "1") (pinfunction "11_1") (pintype "passive"))
      (node (ref "R8") (pin "1") (pinfunction "11_1") (pintype "passive"))
      (node (ref "R9") (pin "1") (pinfunction "11_1") (pintype "passive"))
      (node (ref "U1") (pin "1") (pinfunction "VCC_1") (pintype "passive"))
      (node (ref "U2") (pin "OUT") (pinfunction "OUT_OUT") (pintype "bidirectional"))
    )
    (net (code "2") (name "5V") (class "Default")
      (node (ref "C2") (pin "2") (pinfunction "2_2") (pintype "passive"))
      (node (ref "C3") (pin "2") (pinfunction "2_2") (pintype "passive"))
      (node (ref "C4") (pin "2") (pinfunction "2_2") (pintype "passive"))
      (node (ref "C7") (pin "2") (pinfunction "2_2") (pintype "passive"))
      (node (ref "C8") (pin "2") (pinfunction "2_2") (pintype "passive"))
      (node (ref "C9") (pin "2") (pinfunction "2_2") (pintype "passive"))
      (node (ref "CR2") (pin "2") (pinfunction "OUTPUT_2") (pintype "passive"))
      (node (ref "CR3") (pin "1") (pinfunction "12_1") (pintype "passive"))
      (node (ref "IC1") (pin "18") (pinfunction "AVCC_18") (pintype "bidirectional"))
      (node (ref "IC1") (pin "4") (pinfunction "VCC_4") (pintype "bidirectional"))
      (node (ref "IC1") (pin "6") (pinfunction "VCC_6") (pintype "bidirectional"))
      (node (ref "IC2") (pin "20") (pinfunction "VCC_20") (pintype "power_in"))
      (node (ref "IC2") (pin "4") (pinfunction "VCCIO_4") (pintype "power_in"))
      (node (ref "JP1") (pin "2") (pinfunction "2_2") (pintype "passive"))
      (node (ref "R19") (pin "1") (pinfunction "11_1") (pintype "passive"))
      (node (ref "R20") (pin "1") (pinfunction "11_1") (pintype "passive"))
      (node (ref "R21") (pin "1") (pinfunction "11_1") (pintype "passive"))
      (node (ref "R25") (pin "1") (pinfunction "11_1") (pintype "passive"))
      (node (ref "R26") (pin "1") (pinfunction "11_1") (pintype "passive"))
      (node (ref "R27") (pin "1") (pinfunction "11_1") (pintype "passive"))
      (node (ref "R3") (pin "1") (pinfunction "11_1") (pintype "passive"))
      (node (ref "R38") (pin "1") (pinfunction "11_1") (pintype "passive"))
      (node (ref "R39") (pin "1") (pinfunction "11_1") (pintype "passive"))
      (node (ref "R4") (pin "1") (pinfunction "11_1") (pintype "passive"))
      (node (ref "R40") (pin "1") (pinfunction "11_1") (pintype "passive"))
      (node (ref "R41") (pin "1") (pinfunction "11_1") (pintype "passive"))
      (node (ref "R42") (pin "1") (pinfunction "11_1") (pintype "passive"))
      (node (ref "R43") (pin "1") (pinfunction "11_1") (pintype "passive"))
      (node (ref "R44") (pin "1") (pinfunction "11_1") (pintype "passive"))
      (node (ref "R45") (pin "1") (pinfunction "11_1") (pintype "passive"))
      (node (ref "R46") (pin "1") (pinfunction "11_1") (pintype "passive"))
      (node (ref "R47") (pin "1") (pinfunction "11_1") (pintype "passive"))
      (node (ref "U2") (pin "EN") (pinfunction "EN_EN") (pintype "bidirectional"))
      (node (ref "U2") (pin "IN") (pinfunction "IN_IN") (pintype "bidirectional"))
      (node (ref "U3") (pin "8") (pinfunction "VDD_8") (pintype "power_in"))
      (node (ref "U4") (pin "8") (pinfunction "VDD_8") (pintype "power_in"))
      (node (ref "U5") (pin "8") (pinfunction "VDD_8") (pintype "power_in"))
    )
    (net (code "3") (name "A6") (class "Default")
      (node (ref "IC1") (pin "19") (pinfunction "ADC6_19") (pintype "bidirectional"))
    )
    (net (code "4") (name "A7") (class "Default")
      (node (ref "IC1") (pin "22") (pinfunction "ADC7_22") (pintype "bidirectional"))
    )
    (net (code "5") (name "AREF") (class "Default")
      (node (ref "C15") (pin "2") (pinfunction "2_2") (pintype "passive"))
      (node (ref "IC1") (pin "20") (pinfunction "AREF_20") (pintype "bidirectional"))
    )
    (net (code "6") (name "CS1") (class "Default")
      (node (ref "IC1") (pin "32") (pinfunction "PD2(INT0)_32") (pintype "bidirectional"))
      (node (ref "Q10") (pin "D") (pinfunction "D_D") (pintype "passive"))
      (node (ref "R38") (pin "2") (pinfunction "22_2") (pintype "passive"))
    )
    (net (code "7") (name "CS1_3V") (class "Default")
      (node (ref "F2") (pin "1") (pinfunction "~{CS}_1") (pintype "passive"))
      (node (ref "Q10") (pin "S") (pinfunction "S_S") (pintype "passive"))
      (node (ref "R28") (pin "2") (pinfunction "22_2") (pintype "passive"))
    )
    (net (code "8") (name "CS2") (class "Default")
      (node (ref "IC1") (pin "1") (pinfunction "PD3(INT1)_1") (pintype "bidirectional"))
      (node (ref "Q11") (pin "D") (pinfunction "D_D") (pintype "passive"))
      (node (ref "R39") (pin "2") (pinfunction "22_2") (pintype "passive"))
    )
    (net (code "9") (name "CS2_3V") (class "Default")
      (node (ref "F3") (pin "1") (pinfunction "~{CS}_1") (pintype "passive"))
      (node (ref "Q11") (pin "S") (pinfunction "S_S") (pintype "passive"))
      (node (ref "R29") (pin "2") (pinfunction "22_2") (pintype "passive"))
    )
    (net (code "10") (name "CS3") (class "Default")
      (node (ref "IC1") (pin "2") (pinfunction "PD4(XCK/T0)_2") (pintype "bidirectional"))
      (node (ref "Q12") (pin "D") (pinfunction "D_D") (pintype "passive"))
      (node (ref "R40") (pin "2") (pinfunction "22_2") (pintype "passive"))
    )
    (net (code "11") (name "CS3_3V") (class "Default")
      (node (ref "F4") (pin "1") (pinfunction "~{CS}_1") (pintype "passive"))
      (node (ref "Q12") (pin "S") (pinfunction "S_S") (pintype "passive"))
      (node (ref "R30") (pin "2") (pinfunction "22_2") (pintype "passive"))
    )
    (net (code "12") (name "CS4") (class "Default")
      (node (ref "IC1") (pin "9") (pinfunction "PD5(T1)_9") (pintype "bidirectional"))
      (node (ref "Q13") (pin "D") (pinfunction "D_D") (pintype "passive"))
      (node (ref "R41") (pin "2") (pinfunction "22_2") (pintype "passive"))
    )
    (net (code "13") (name "CS4_3V") (class "Default")
      (node (ref "F5") (pin "1") (pinfunction "~{CS}_1") (pintype "passive"))
      (node (ref "Q13") (pin "S") (pinfunction "S_S") (pintype "passive"))
      (node (ref "R31") (pin "2") (pinfunction "22_2") (pintype "passive"))
    )
    (net (code "14") (name "CS5") (class "Default")
      (node (ref "IC1") (pin "10") (pinfunction "PD6(AIN0)_10") (pintype "bidirectional"))
      (node (ref "Q14") (pin "D") (pinfunction "D_D") (pintype "passive"))
      (node (ref "R42") (pin "2") (pinfunction "22_2") (pintype "passive"))
    )
    (net (code "15") (name "CS5_3V") (class "Default")
      (node (ref "F6") (pin "1") (pinfunction "~{CS}_1") (pintype "passive"))
      (node (ref "Q14") (pin "S") (pinfunction "S_S") (pintype "passive"))
      (node (ref "R32") (pin "2") (pinfunction "22_2") (pintype "passive"))
    )
    (net (code "16") (name "CS6") (class "Default")
      (node (ref "IC1") (pin "11") (pinfunction "PD7(AIN1)_11") (pintype "bidirectional"))
      (node (ref "Q15") (pin "D") (pinfunction "D_D") (pintype "passive"))
      (node (ref "R43") (pin "2") (pinfunction "22_2") (pintype "passive"))
    )
    (net (code "17") (name "CS6_3V") (class "Default")
      (node (ref "F7") (pin "1") (pinfunction "~{CS}_1") (pintype "passive"))
      (node (ref "Q15") (pin "S") (pinfunction "S_S") (pintype "passive"))
      (node (ref "R33") (pin "2") (pinfunction "22_2") (pintype "passive"))
    )
    (net (code "18") (name "CS7") (class "Default")
      (node (ref "IC1") (pin "23") (pinfunction "PC0(ADC0)_23") (pintype "bidirectional"))
      (node (ref "Q16") (pin "D") (pinfunction "D_D") (pintype "passive"))
      (node (ref "R44") (pin "2") (pinfunction "22_2") (pintype "passive"))
    )
    (net (code "19") (name "CS7_3V") (class "Default")
      (node (ref "F8") (pin "1") (pinfunction "~{CS}_1") (pintype "passive"))
      (node (ref "Q16") (pin "S") (pinfunction "S_S") (pintype "passive"))
      (node (ref "R34") (pin "2") (pinfunction "22_2") (pintype "passive"))
    )
    (net (code "20") (name "CS8") (class "Default")
      (node (ref "IC1") (pin "24") (pinfunction "PC1(ADC1)_24") (pintype "bidirectional"))
      (node (ref "Q17") (pin "D") (pinfunction "D_D") (pintype "passive"))
      (node (ref "R45") (pin "2") (pinfunction "22_2") (pintype "passive"))
    )
    (net (code "21") (name "CS8_3V") (class "Default")
      (node (ref "F9") (pin "1") (pinfunction "~{CS}_1") (pintype "passive"))
      (node (ref "Q17") (pin "S") (pinfunction "S_S") (pintype "passive"))
      (node (ref "R35") (pin "2") (pinfunction "22_2") (pintype "passive"))
    )
    (net (code "22") (name "CS9") (class "Default")
      (node (ref "IC1") (pin "25") (pinfunction "PC2(ADC2)_25") (pintype "bidirectional"))
      (node (ref "Q18") (pin "D") (pinfunction "D_D") (pintype "passive"))
      (node (ref "R46") (pin "2") (pinfunction "22_2") (pintype "passive"))
    )
    (net (code "23") (name "CS9_3V") (class "Default")
      (node (ref "F10") (pin "1") (pinfunction "~{CS}_1") (pintype "passive"))
      (node (ref "Q18") (pin "S") (pinfunction "S_S") (pintype "passive"))
      (node (ref "R36") (pin "2") (pinfunction "22_2") (pintype "passive"))
    )
    (net (code "24") (name "CS10") (class "Default")
      (node (ref "IC1") (pin "26") (pinfunction "PC3(ADC3)_26") (pintype "bidirectional"))
      (node (ref "Q19") (pin "D") (pinfunction "D_D") (pintype "passive"))
      (node (ref "R47") (pin "2") (pinfunction "22_2") (pintype "passive"))
    )
    (net (code "25") (name "CS10_3V") (class "Default")
      (node (ref "F11") (pin "1") (pinfunction "~{CS}_1") (pintype "passive"))
      (node (ref "Q19") (pin "S") (pinfunction "S_S") (pintype "passive"))
      (node (ref "R37") (pin "2") (pinfunction "22_2") (pintype "passive"))
    )
    (net (code "26") (name "D0{slash}RX") (class "Default")
      (node (ref "IC1") (pin "30") (pinfunction "PD0(RXD)_30") (pintype "bidirectional"))
      (node (ref "Q2") (pin "D") (pinfunction "D_D") (pintype "passive"))
      (node (ref "R4") (pin "2") (pinfunction "22_2") (pintype "passive"))
    )
    (net (code "27") (name "D0{slash}RX_3.3V") (class "Default")
      (node (ref "Q2") (pin "S") (pinfunction "S_S") (pintype "passive"))
      (node (ref "R2") (pin "2") (pinfunction "22_2") (pintype "passive"))
      (node (ref "U1") (pin "3") (pinfunction "DI_3") (pintype "passive"))
    )
    (net (code "28") (name "D1{slash}TX") (class "Default")
      (node (ref "IC1") (pin "31") (pinfunction "PD1(TXD)_31") (pintype "bidirectional"))
      (node (ref "Q1") (pin "D") (pinfunction "D_D") (pintype "passive"))
      (node (ref "R3") (pin "2") (pinfunction "22_2") (pintype "passive"))
    )
    (net (code "29") (name "D1{slash}TX_3.3V") (class "Default")
      (node (ref "Q1") (pin "S") (pinfunction "S_S") (pintype "passive"))
      (node (ref "R1") (pin "2") (pinfunction "22_2") (pintype "passive"))
      (node (ref "U1") (pin "2") (pinfunction "RO_2") (pintype "passive"))
    )
    (net (code "30") (name "D8") (class "Default")
      (node (ref "IC1") (pin "12") (pinfunction "PB0(ICP)_12") (pintype "bidirectional"))
      (node (ref "Q7") (pin "D") (pinfunction "D_D") (pintype "passive"))
      (node (ref "R25") (pin "2") (pinfunction "22_2") (pintype "passive"))
    )
    (net (code "31") (name "D8_3V") (class "Default")
      (node (ref "J$2") (pin "10") (pinfunction "10_10") (pintype "passive"))
      (node (ref "J$2") (pin "7") (pinfunction "7_7") (pintype "passive"))
      (node (ref "Q7") (pin "S") (pinfunction "S_S") (pintype "passive"))
      (node (ref "R22") (pin "2") (pinfunction "22_2") (pintype "passive"))
    )
    (net (code "32") (name "D9") (class "Default")
      (node (ref "IC1") (pin "13") (pinfunction "PB1(OC1A)_13") (pintype "bidirectional"))
      (node (ref "Q8") (pin "D") (pinfunction "D_D") (pintype "passive"))
      (node (ref "R26") (pin "2") (pinfunction "22_2") (pintype "passive"))
    )
    (net (code "33") (name "D9_3V") (class "Default")
      (node (ref "J$2") (pin "11") (pinfunction "11_11") (pintype "passive"))
      (node (ref "J$2") (pin "8") (pinfunction "8_8") (pintype "passive"))
      (node (ref "Q8") (pin "S") (pinfunction "S_S") (pintype "passive"))
      (node (ref "R23") (pin "2") (pinfunction "22_2") (pintype "passive"))
    )
    (net (code "34") (name "D10") (class "Default")
      (node (ref "IC1") (pin "14") (pinfunction "PB2(SS/OC1B)_14") (pintype "bidirectional"))
      (node (ref "Q9") (pin "D") (pinfunction "D_D") (pintype "passive"))
      (node (ref "R27") (pin "2") (pinfunction "22_2") (pintype "passive"))
    )
    (net (code "35") (name "D10_3V") (class "Default")
      (node (ref "J$2") (pin "12") (pinfunction "12_12") (pintype "passive"))
      (node (ref "J$2") (pin "9") (pinfunction "9_9") (pintype "passive"))
      (node (ref "Q9") (pin "S") (pinfunction "S_S") (pintype "passive"))
      (node (ref "R24") (pin "2") (pinfunction "22_2") (pintype "passive"))
    )
    (net (code "36") (name "D11{slash}MOSI") (class "Default")
      (node (ref "IC1") (pin "15") (pinfunction "PB3(MOSI/OC2)_15") (pintype "bidirectional"))
      (node (ref "J$2") (pin "3") (pinfunction "3_3") (pintype "passive"))
      (node (ref "J$2") (pin "6") (pinfunction "6_6") (pintype "passive"))
      (node (ref "JP1") (pin "4") (pinfunction "4_4") (pintype "passive"))
      (node (ref "Q6") (pin "D") (pinfunction "D_D") (pintype "passive"))
      (node (ref "R21") (pin "2") (pinfunction "22_2") (pintype "passive"))
    )
    (net (code "37") (name "D12{slash}MISO") (class "Default")
      (node (ref "IC1") (pin "16") (pinfunction "PB4(MISO)_16") (pintype "bidirectional"))
      (node (ref "J$2") (pin "2") (pinfunction "2_2") (pintype "passive"))
      (node (ref "J$2") (pin "5") (pinfunction "5_5") (pintype "passive"))
      (node (ref "JP1") (pin "1") (pinfunction "1_1") (pintype "passive"))
      (node (ref "Q5") (pin "D") (pinfunction "D_D") (pintype "passive"))
      (node (ref "R20") (pin "2") (pinfunction "22_2") (pintype "passive"))
    )
    (net (code "38") (name "D13{slash}SCK") (class "Default")
      (node (ref "IC1") (pin "17") (pinfunction "PB5(SCK)_17") (pintype "bidirectional"))
      (node (ref "J$2") (pin "1") (pinfunction "1_1") (pintype "passive"))
      (node (ref "J$2") (pin "4") (pinfunction "4_4") (pintype "passive"))
      (node (ref "JP1") (pin "3") (pinfunction "3_3") (pintype "passive"))
      (node (ref "Q4") (pin "D") (pinfunction "D_D") (pintype "passive"))
      (node (ref "R19") (pin "2") (pinfunction "22_2") (pintype "passive"))
    )
    (net (code "39") (name "GND") (class "Default")
      (node (ref "C1") (pin "1") (pinfunction "1_1") (pintype "passive"))
      (node (ref "C10") (pin "1") (pinfunction "1_1") (pintype "passive"))
      (node (ref "C11") (pin "1") (pinfunction "1_1") (pintype "passive"))
      (node (ref "C12") (pin "1") (pinfunction "1_1") (pintype "passive"))
      (node (ref "C13") (pin "1") (pinfunction "1_1") (pintype "passive"))
      (node (ref "C14") (pin "1") (pinfunction "1_1") (pintype "passive"))
      (node (ref "C15") (pin "1") (pinfunction "1_1") (pintype "passive"))
      (node (ref "C16") (pin "1") (pinfunction "1_1") (pintype "passive"))
      (node (ref "C17") (pin "1") (pinfunction "1_1") (pintype "passive"))
      (node (ref "C18") (pin "1") (pinfunction "1_1") (pintype "passive"))
      (node (ref "C19") (pin "1") (pinfunction "1_1") (pintype "passive"))
      (node (ref "C2") (pin "1") (pinfunction "1_1") (pintype "passive"))
      (node (ref "C20") (pin "1") (pinfunction "1_1") (pintype "passive"))
      (node (ref "C21") (pin "1") (pinfunction "1_1") (pintype "passive"))
      (node (ref "C22") (pin "1") (pinfunction "1_1") (pintype "passive"))
      (node (ref "C23") (pin "1") (pinfunction "1_1") (pintype "passive"))
      (node (ref "C24") (pin "1") (pinfunction "1_1") (pintype "passive"))
      (node (ref "C25") (pin "1") (pinfunction "1_1") (pintype "passive"))
      (node (ref "C3") (pin "1") (pinfunction "1_1") (pintype "passive"))
      (node (ref "C4") (pin "1") (pinfunction "1_1") (pintype "passive"))
      (node (ref "C5") (pin "1") (pinfunction "1_1") (pintype "passive"))
      (node (ref "C7") (pin "1") (pinfunction "1_1") (pintype "passive"))
      (node (ref "C8") (pin "1") (pinfunction "1_1") (pintype "passive"))
      (node (ref "C9") (pin "1") (pinfunction "1_1") (pintype "passive"))
      (node (ref "CR2") (pin "1") (pinfunction "GROUND_1") (pintype "passive"))
      (node (ref "F10") (pin "4") (pinfunction "VSS_4") (pintype "passive"))
      (node (ref "F11") (pin "4") (pinfunction "VSS_4") (pintype "passive"))
      (node (ref "F2") (pin "4") (pinfunction "VSS_4") (pintype "passive"))
      (node (ref "F3") (pin "4") (pinfunction "VSS_4") (pintype "passive"))
      (node (ref "F4") (pin "4") (pinfunction "VSS_4") (pintype "passive"))
      (node (ref "F5") (pin "4") (pinfunction "VSS_4") (pintype "passive"))
      (node (ref "F6") (pin "4") (pinfunction "VSS_4") (pintype "passive"))
      (node (ref "F7") (pin "4") (pinfunction "VSS_4") (pintype "passive"))
      (node (ref "F8") (pin "4") (pinfunction "VSS_4") (pintype "passive"))
      (node (ref "F9") (pin "4") (pinfunction "VSS_4") (pintype "passive"))
      (node (ref "IC1") (pin "21") (pinfunction "AGND_21") (pintype "bidirectional"))
      (node (ref "IC1") (pin "3") (pinfunction "GND_3") (pintype "bidirectional"))
      (node (ref "IC1") (pin "5") (pinfunction "GND_5") (pintype "bidirectional"))
      (node (ref "IC2") (pin "18") (pinfunction "GND2_18") (pintype "power_in"))
      (node (ref "IC2") (pin "21") (pinfunction "GND3_21") (pintype "power_in"))
      (node (ref "IC2") (pin "25") (pinfunction "AGND_25") (pintype "power_in"))
      (node (ref "IC2") (pin "26") (pinfunction "TEST_26") (pintype "bidirectional"))
      (node (ref "IC2") (pin "7") (pinfunction "GND1_7") (pintype "power_in"))
      (node (ref "J$1") (pin "11") (pinfunction "11_11") (pintype "passive"))
      (node (ref "J$1") (pin "7") (pinfunction "7_7") (pintype "passive"))
      (node (ref "J$1") (pin "9") (pinfunction "9_9") (pintype "passive"))
      (node (ref "J$3") (pin "1") (pinfunction "1_1") (pintype "passive"))
      (node (ref "J$3") (pin "2") (pinfunction "2_2") (pintype "passive"))
      (node (ref "J$3") (pin "3") (pinfunction "3_3") (pintype "passive"))
      (node (ref "JP1") (pin "6") (pinfunction "6_6") (pintype "passive"))
      (node (ref "U1") (pin "4") (pinfunction "GND_4") (pintype "passive"))
      (node (ref "U2") (pin "GND") (pinfunction "GND_GND") (pintype "bidirectional"))
      (node (ref "U3") (pin "4") (pinfunction "GND_4") (pintype "passive"))
      (node (ref "U4") (pin "4") (pinfunction "GND_4") (pintype "passive"))
      (node (ref "U5") (pin "4") (pinfunction "GND_4") (pintype "passive"))
      (node (ref "USB1") (pin "1") (pinfunction "GND_1") (pintype "passive"))
      (node (ref "USB1") (pin "6") (pinfunction "SH1_6") (pintype "passive"))
      (node (ref "USB1") (pin "7") (pinfunction "SH2_7") (pintype "passive"))
      (node (ref "USB1") (pin "8") (pinfunction "SH3_8") (pintype "passive"))
      (node (ref "USB1") (pin "9") (pinfunction "SH4_9") (pintype "passive"))
    )
    (net (code "40") (name "MISO_3V") (class "Default")
      (node (ref "F10") (pin "2") (pinfunction "SO_2") (pintype "passive"))
      (node (ref "F11") (pin "2") (pinfunction "SO_2") (pintype "passive"))
      (node (ref "F2") (pin "2") (pinfunction "SO_2") (pintype "passive"))
      (node (ref "F3") (pin "2") (pinfunction "SO_2") (pintype "passive"))
      (node (ref "F4") (pin "2") (pinfunction "SO_2") (pintype "passive"))
      (node (ref "F5") (pin "2") (pinfunction "SO_2") (pintype "passive"))
      (node (ref "F6") (pin "2") (pinfunction "SO_2") (pintype "passive"))
      (node (ref "F7") (pin "2") (pinfunction "SO_2") (pintype "passive"))
      (node (ref "F8") (pin "2") (pinfunction "SO_2") (pintype "passive"))
      (node (ref "F9") (pin "2") (pinfunction "SO_2") (pintype "passive"))
      (node (ref "Q5") (pin "S") (pinfunction "S_S") (pintype "passive"))
      (node (ref "R17") (pin "2") (pinfunction "22_2") (pintype "passive"))
    )
    (net (code "41") (name "MOSI_3V") (class "Default")
      (node (ref "F10") (pin "5") (pinfunction "SI_5") (pintype "passive"))
      (node (ref "F11") (pin "5") (pinfunction "SI_5") (pintype "passive"))
      (node (ref "F2") (pin "5") (pinfunction "SI_5") (pintype "passive"))
      (node (ref "F3") (pin "5") (pinfunction "SI_5") (pintype "passive"))
      (node (ref "F4") (pin "5") (pinfunction "SI_5") (pintype "passive"))
      (node (ref "F5") (pin "5") (pinfunction "SI_5") (pintype "passive"))
      (node (ref "F6") (pin "5") (pinfunction "SI_5") (pintype "passive"))
      (node (ref "F7") (pin "5") (pinfunction "SI_5") (pintype "passive"))
      (node (ref "F8") (pin "5") (pinfunction "SI_5") (pintype "passive"))
      (node (ref "F9") (pin "5") (pinfunction "SI_5") (pintype "passive"))
      (node (ref "Q6") (pin "S") (pinfunction "S_S") (pintype "passive"))
      (node (ref "R18") (pin "2") (pinfunction "22_2") (pintype "passive"))
    )
    (net (code "42") (name "Net-(F2-~{HOLD})") (class "Default")
      (node (ref "F2") (pin "7") (pinfunction "~{HOLD}_7") (pintype "passive"))
      (node (ref "R6") (pin "2") (pinfunction "22_2") (pintype "passive"))
    )
    (net (code "43") (name "Net-(F3-~{HOLD})") (class "Default")
      (node (ref "F3") (pin "7") (pinfunction "~{HOLD}_7") (pintype "passive"))
      (node (ref "R7") (pin "2") (pinfunction "22_2") (pintype "passive"))
    )
    (net (code "44") (name "Net-(F4-~{HOLD})") (class "Default")
      (node (ref "F4") (pin "7") (pinfunction "~{HOLD}_7") (pintype "passive"))
      (node (ref "R8") (pin "2") (pinfunction "22_2") (pintype "passive"))
    )
    (net (code "45") (name "Net-(F5-~{HOLD})") (class "Default")
      (node (ref "F5") (pin "7") (pinfunction "~{HOLD}_7") (pintype "passive"))
      (node (ref "R9") (pin "2") (pinfunction "22_2") (pintype "passive"))
    )
    (net (code "46") (name "Net-(F6-~{HOLD})") (class "Default")
      (node (ref "F6") (pin "7") (pinfunction "~{HOLD}_7") (pintype "passive"))
      (node (ref "R10") (pin "2") (pinfunction "22_2") (pintype "passive"))
    )
    (net (code "47") (name "Net-(F7-~{HOLD})") (class "Default")
      (node (ref "F7") (pin "7") (pinfunction "~{HOLD}_7") (pintype "passive"))
      (node (ref "R11") (pin "2") (pinfunction "22_2") (pintype "passive"))
    )
    (net (code "48") (name "Net-(F8-~{HOLD})") (class "Default")
      (node (ref "F8") (pin "7") (pinfunction "~{HOLD}_7") (pintype "passive"))
      (node (ref "R12") (pin "2") (pinfunction "22_2") (pintype "passive"))
    )
    (net (code "49") (name "Net-(F9-~{HOLD})") (class "Default")
      (node (ref "F9") (pin "7") (pinfunction "~{HOLD}_7") (pintype "passive"))
      (node (ref "R13") (pin "2") (pinfunction "22_2") (pintype "passive"))
    )
    (net (code "50") (name "Net-(F10-~{HOLD})") (class "Default")
      (node (ref "F10") (pin "7") (pinfunction "~{HOLD}_7") (pintype "passive"))
      (node (ref "R14") (pin "2") (pinfunction "22_2") (pintype "passive"))
    )
    (net (code "51") (name "Net-(F11-~{HOLD})") (class "Default")
      (node (ref "F11") (pin "7") (pinfunction "~{HOLD}_7") (pintype "passive"))
      (node (ref "R15") (pin "2") (pinfunction "22_2") (pintype "passive"))
    )
    (net (code "52") (name "Net-(IC2-DTR#)") (class "Default")
      (node (ref "C6") (pin "2") (pinfunction "2_2") (pintype "passive"))
      (node (ref "IC2") (pin "2") (pinfunction "DTR#_2") (pintype "output"))
    )
    (net (code "53") (name "Net-(IC2-USBDM)") (class "Default")
      (node (ref "IC2") (pin "16") (pinfunction "USBDM_16") (pintype "bidirectional"))
      (node (ref "USB1") (pin "4") (pinfunction "D-_4") (pintype "bidirectional"))
    )
    (net (code "54") (name "Net-(IC2-USBDP)") (class "Default")
      (node (ref "IC2") (pin "15") (pinfunction "USBDP_15") (pintype "bidirectional"))
      (node (ref "USB1") (pin "3") (pinfunction "D+_3") (pintype "bidirectional"))
    )
    (net (code "55") (name "Net-(USB1-VBUS)") (class "Default")
      (node (ref "F1") (pin "2") (pinfunction "2_2") (pintype "passive"))
      (node (ref "USB1") (pin "5") (pinfunction "VBUS_5") (pintype "power_in"))
    )
    (net (code "56") (name "RESET") (class "Default")
      (node (ref "C6") (pin "1") (pinfunction "1_1") (pintype "passive"))
      (node (ref "IC1") (pin "29") (pinfunction "PC6(/RESET)_29") (pintype "bidirectional"))
      (node (ref "J$1") (pin "5") (pinfunction "5_5") (pintype "passive"))
      (node (ref "J$1") (pin "6") (pinfunction "6_6") (pintype "passive"))
      (node (ref "JP1") (pin "5") (pinfunction "5_5") (pintype "passive"))
    )
    (net (code "57") (name "RX") (class "Default")
      (node (ref "IC2") (pin "1") (pinfunction "TXD_1") (pintype "output"))
    )
    (net (code "58") (name "RX+") (class "Default")
      (node (ref "J$1") (pin "1") (pinfunction "1_1") (pintype "passive"))
      (node (ref "U1") (pin "8") (pinfunction "A_8") (pintype "passive"))
    )
    (net (code "59") (name "RX-") (class "Default")
      (node (ref "J$1") (pin "2") (pinfunction "2_2") (pintype "passive"))
      (node (ref "U1") (pin "7") (pinfunction "B_7") (pintype "passive"))
    )
    (net (code "60") (name "SCK_3V") (class "Default")
      (node (ref "F10") (pin "6") (pinfunction "SCK_6") (pintype "passive"))
      (node (ref "F11") (pin "6") (pinfunction "SCK_6") (pintype "passive"))
      (node (ref "F2") (pin "6") (pinfunction "SCK_6") (pintype "passive"))
      (node (ref "F3") (pin "6") (pinfunction "SCK_6") (pintype "passive"))
      (node (ref "F4") (pin "6") (pinfunction "SCK_6") (pintype "passive"))
      (node (ref "F5") (pin "6") (pinfunction "SCK_6") (pintype "passive"))
      (node (ref "F6") (pin "6") (pinfunction "SCK_6") (pintype "passive"))
      (node (ref "F7") (pin "6") (pinfunction "SCK_6") (pintype "passive"))
      (node (ref "F8") (pin "6") (pinfunction "SCK_6") (pintype "passive"))
      (node (ref "F9") (pin "6") (pinfunction "SCK_6") (pintype "passive"))
      (node (ref "Q4") (pin "S") (pinfunction "S_S") (pintype "passive"))
      (node (ref "R16") (pin "2") (pinfunction "22_2") (pintype "passive"))
    )
    (net (code "61") (name "SCL") (class "Default")
      (node (ref "IC1") (pin "28") (pinfunction "PC5(ADC5/SCL)_28") (pintype "bidirectional"))
      (node (ref "J$3") (pin "11") (pinfunction "11_11") (pintype "passive"))
      (node (ref "J$3") (pin "5") (pinfunction "5_5") (pintype "passive"))
      (node (ref "J$3") (pin "7") (pinfunction "7_7") (pintype "passive"))
      (node (ref "J$3") (pin "9") (pinfunction "9_9") (pintype "passive"))
    )
    (net (code "62") (name "SDA") (class "Default")
      (node (ref "IC1") (pin "27") (pinfunction "PC4(ADC4/SDA)_27") (pintype "bidirectional"))
      (node (ref "J$3") (pin "10") (pinfunction "10_10") (pintype "passive"))
      (node (ref "J$3") (pin "12") (pinfunction "12_12") (pintype "passive"))
      (node (ref "J$3") (pin "6") (pinfunction "6_6") (pintype "passive"))
      (node (ref "J$3") (pin "8") (pinfunction "8_8") (pintype "passive"))
    )
    (net (code "63") (name "TEMP") (class "Default")
      (node (ref "J$3") (pin "4") (pinfunction "4_4") (pintype "passive"))
      (node (ref "U3") (pin "1") (pinfunction "DQ_1") (pintype "bidirectional"))
      (node (ref "U4") (pin "1") (pinfunction "DQ_1") (pintype "bidirectional"))
      (node (ref "U5") (pin "1") (pinfunction "DQ_1") (pintype "bidirectional"))
    )
    (net (code "64") (name "TX") (class "Default")
      (node (ref "IC2") (pin "5") (pinfunction "RXD_5") (pintype "input"))
    )
    (net (code "65") (name "TX+") (class "Default")
      (node (ref "J$1") (pin "3") (pinfunction "3_3") (pintype "passive"))
      (node (ref "U1") (pin "6") (pinfunction "Z_6") (pintype "passive"))
    )
    (net (code "66") (name "TX-") (class "Default")
      (node (ref "J$1") (pin "4") (pinfunction "4_4") (pintype "passive"))
      (node (ref "U1") (pin "5") (pinfunction "Y_5") (pintype "passive"))
    )
    (net (code "67") (name "VIN") (class "Default")
      (node (ref "C1") (pin "2") (pinfunction "2_2") (pintype "passive"))
      (node (ref "CR1") (pin "1") (pinfunction "12_1") (pintype "passive"))
      (node (ref "CR2") (pin "3") (pinfunction "INPUT_3") (pintype "passive"))
      (node (ref "J$1") (pin "12") (pinfunction "12_12") (pintype "passive"))
    )
    (net (code "68") (name "V_USB") (class "Default")
      (node (ref "C12") (pin "2") (pinfunction "2_2") (pintype "passive"))
      (node (ref "C13") (pin "2") (pinfunction "2_2") (pintype "passive"))
      (node (ref "CR3") (pin "2") (pinfunction "21_2") (pintype "passive"))
      (node (ref "F1") (pin "1") (pinfunction "1_1") (pintype "passive"))
    )
    (net (code "69") (name "XTAL1") (class "Default")
      (node (ref "C14") (pin "2") (pinfunction "2_2") (pintype "passive"))
      (node (ref "IC1") (pin "7") (pinfunction "PB6(XTAL1/TOSC1)_7") (pintype "bidirectional"))
      (node (ref "Q3") (pin "1") (pinfunction "1_1") (pintype "bidirectional"))
      (node (ref "R5") (pin "2") (pinfunction "22_2") (pintype "passive"))
    )
    (net (code "70") (name "XTAL2") (class "Default")
      (node (ref "C11") (pin "2") (pinfunction "2_2") (pintype "passive"))
      (node (ref "IC1") (pin "8") (pinfunction "PB7(XTAL2/TOSC2)_8") (pintype "bidirectional"))
      (node (ref "Q3") (pin "2") (pinfunction "2_2") (pintype "bidirectional"))
      (node (ref "R5") (pin "1") (pinfunction "11_1") (pintype "passive"))
    )
    (net (code "71") (name "unconnected-(CR1-21-Pad2)") (class "Default")
      (node (ref "CR1") (pin "2") (pinfunction "21_2") (pintype "passive"))
    )
    (net (code "72") (name "unconnected-(F2-~{WP}-Pad3)") (class "Default")
      (node (ref "F2") (pin "3") (pinfunction "~{WP}_3") (pintype "passive"))
    )
    (net (code "73") (name "unconnected-(F3-~{WP}-Pad3)") (class "Default")
      (node (ref "F3") (pin "3") (pinfunction "~{WP}_3") (pintype "passive"))
    )
    (net (code "74") (name "unconnected-(F4-~{WP}-Pad3)") (class "Default")
      (node (ref "F4") (pin "3") (pinfunction "~{WP}_3") (pintype "passive"))
    )
    (net (code "75") (name "unconnected-(F5-~{WP}-Pad3)") (class "Default")
      (node (ref "F5") (pin "3") (pinfunction "~{WP}_3") (pintype "passive"))
    )
    (net (code "76") (name "unconnected-(F6-~{WP}-Pad3)") (class "Default")
      (node (ref "F6") (pin "3") (pinfunction "~{WP}_3") (pintype "passive"))
    )
    (net (code "77") (name "unconnected-(F7-~{WP}-Pad3)") (class "Default")
      (node (ref "F7") (pin "3") (pinfunction "~{WP}_3") (pintype "passive"))
    )
    (net (code "78") (name "unconnected-(F8-~{WP}-Pad3)") (class "Default")
      (node (ref "F8") (pin "3") (pinfunction "~{WP}_3") (pintype "passive"))
    )
    (net (code "79") (name "unconnected-(F9-~{WP}-Pad3)") (class "Default")
      (node (ref "F9") (pin "3") (pinfunction "~{WP}_3") (pintype "passive"))
    )
    (net (code "80") (name "unconnected-(F10-~{WP}-Pad3)") (class "Default")
      (node (ref "F10") (pin "3") (pinfunction "~{WP}_3") (pintype "passive"))
    )
    (net (code "81") (name "unconnected-(F11-~{WP}-Pad3)") (class "Default")
      (node (ref "F11") (pin "3") (pinfunction "~{WP}_3") (pintype "passive"))
    )
    (net (code "82") (name "unconnected-(H1-MOUNT-PadB3,2)") (class "Default")
      (node (ref "H1") (pin "B3,2") (pinfunction "MOUNT_B3,2") (pintype "passive"))
    )
    (net (code "83") (name "unconnected-(H2-MOUNT-PadB3,2)") (class "Default")
      (node (ref "H2") (pin "B3,2") (pinfunction "MOUNT_B3,2") (pintype "passive"))
    )
    (net (code "84") (name "unconnected-(H3-MOUNT-PadB3,2)") (class "Default")
      (node (ref "H3") (pin "B3,2") (pinfunction "MOUNT_B3,2") (pintype "passive"))
    )
    (net (code "85") (name "unconnected-(H4-MOUNT-PadB3,2)") (class "Default")
      (node (ref "H4") (pin "B3,2") (pinfunction "MOUNT_B3,2") (pintype "passive"))
    )
    (net (code "86") (name "unconnected-(IC2-CBUS0-Pad23)") (class "Default")
      (node (ref "IC2") (pin "23") (pinfunction "CBUS0_23") (pintype "bidirectional"))
    )
    (net (code "87") (name "unconnected-(IC2-CBUS1-Pad22)") (class "Default")
      (node (ref "IC2") (pin "22") (pinfunction "CBUS1_22") (pintype "bidirectional"))
    )
    (net (code "88") (name "unconnected-(IC2-CBUS2-Pad13)") (class "Default")
      (node (ref "IC2") (pin "13") (pinfunction "CBUS2_13") (pintype "bidirectional"))
    )
    (net (code "89") (name "unconnected-(IC2-CBUS3-Pad14)") (class "Default")
      (node (ref "IC2") (pin "14") (pinfunction "CBUS3_14") (pintype "bidirectional"))
    )
    (net (code "90") (name "unconnected-(IC2-CBUS4-Pad12)") (class "Default")
      (node (ref "IC2") (pin "12") (pinfunction "CBUS4_12") (pintype "bidirectional"))
    )
    (net (code "91") (name "unconnected-(IC2-CTS#-Pad11)") (class "Default")
      (node (ref "IC2") (pin "11") (pinfunction "CTS#_11") (pintype "bidirectional"))
    )
    (net (code "92") (name "unconnected-(IC2-DCD#-Pad10)") (class "Default")
      (node (ref "IC2") (pin "10") (pinfunction "DCD#_10") (pintype "bidirectional"))
    )
    (net (code "93") (name "unconnected-(IC2-DSR#-Pad9)") (class "Default")
      (node (ref "IC2") (pin "9") (pinfunction "DSR#_9") (pintype "bidirectional"))
    )
    (net (code "94") (name "unconnected-(IC2-NC1-Pad8)") (class "Default")
      (node (ref "IC2") (pin "8") (pinfunction "NC1_8") (pintype "bidirectional"))
    )
    (net (code "95") (name "unconnected-(IC2-NC2-Pad24)") (class "Default")
      (node (ref "IC2") (pin "24") (pinfunction "NC2_24") (pintype "no_connect"))
    )
    (net (code "96") (name "unconnected-(IC2-OSCI-Pad27)") (class "Default")
      (node (ref "IC2") (pin "27") (pinfunction "OSCI_27") (pintype "bidirectional"))
    )
    (net (code "97") (name "unconnected-(IC2-OSCO-Pad28)") (class "Default")
      (node (ref "IC2") (pin "28") (pinfunction "OSCO_28") (pintype "output"))
    )
    (net (code "98") (name "unconnected-(IC2-RESET#-Pad19)") (class "Default")
      (node (ref "IC2") (pin "19") (pinfunction "RESET#_19") (pintype "bidirectional"))
    )
    (net (code "99") (name "unconnected-(IC2-RI#-Pad6)") (class "Default")
      (node (ref "IC2") (pin "6") (pinfunction "RI#_6") (pintype "bidirectional"))
    )
    (net (code "100") (name "unconnected-(IC2-RTS#-Pad3)") (class "Default")
      (node (ref "IC2") (pin "3") (pinfunction "RTS#_3") (pintype "output"))
    )
    (net (code "101") (name "unconnected-(U2-P4-PadNC{slash}ADJ)") (class "Default")
      (node (ref "U2") (pin "NC/ADJ") (pinfunction "P4_NC/ADJ") (pintype "bidirectional"))
    )
    (net (code "102") (name "unconnected-(USB1-ID-Pad2)") (class "Default")
      (node (ref "USB1") (pin "2") (pinfunction "ID_2") (pintype "bidirectional"))
    )
  )
)
